# iit_hawkrod_main_board.net
KiCad netlist of a schematic drawn in EAGLE
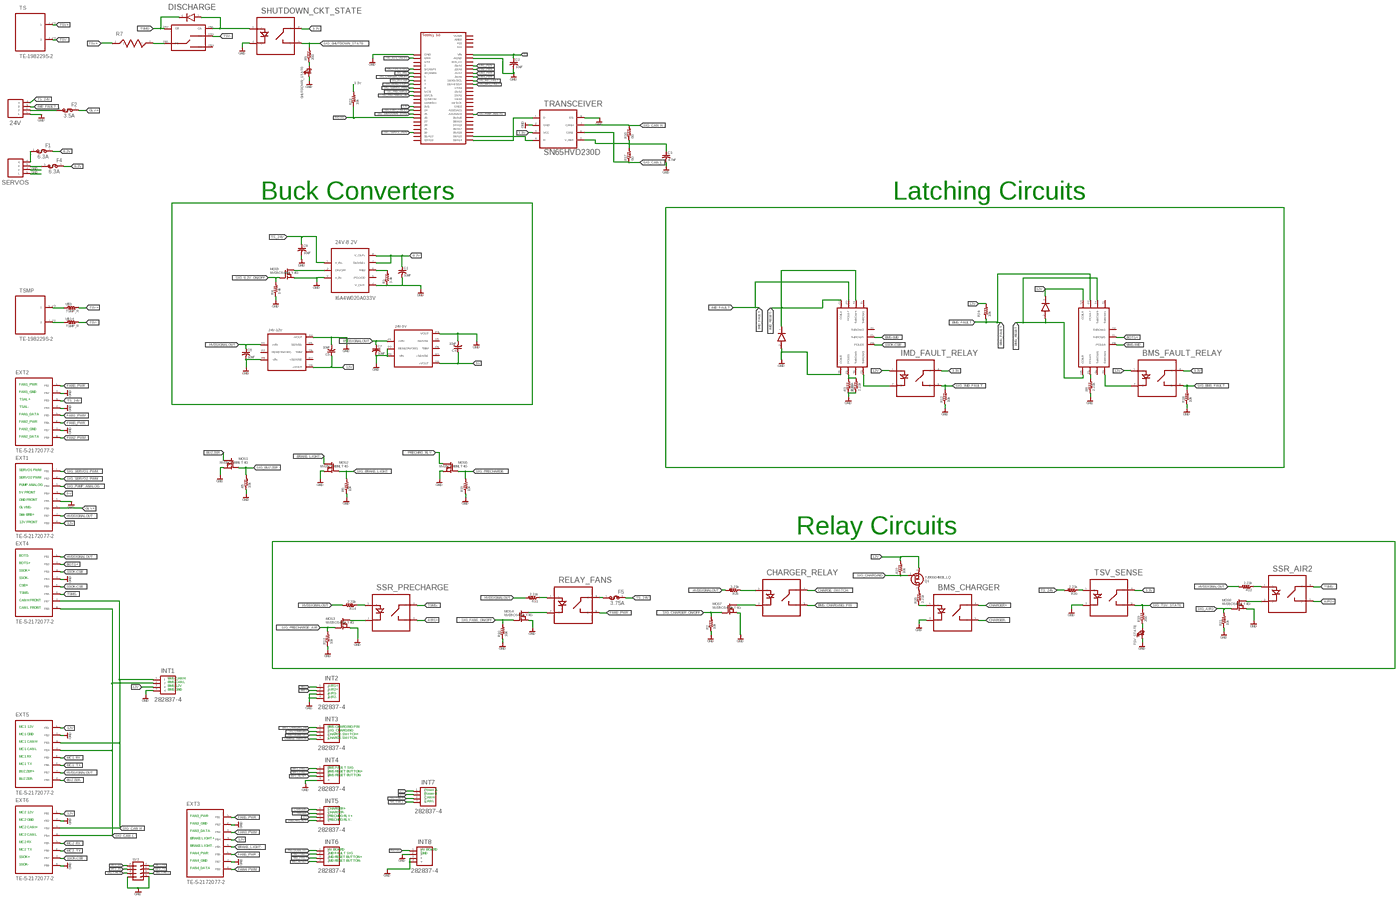
[diagram p0: schematic, sheet 1, overview]
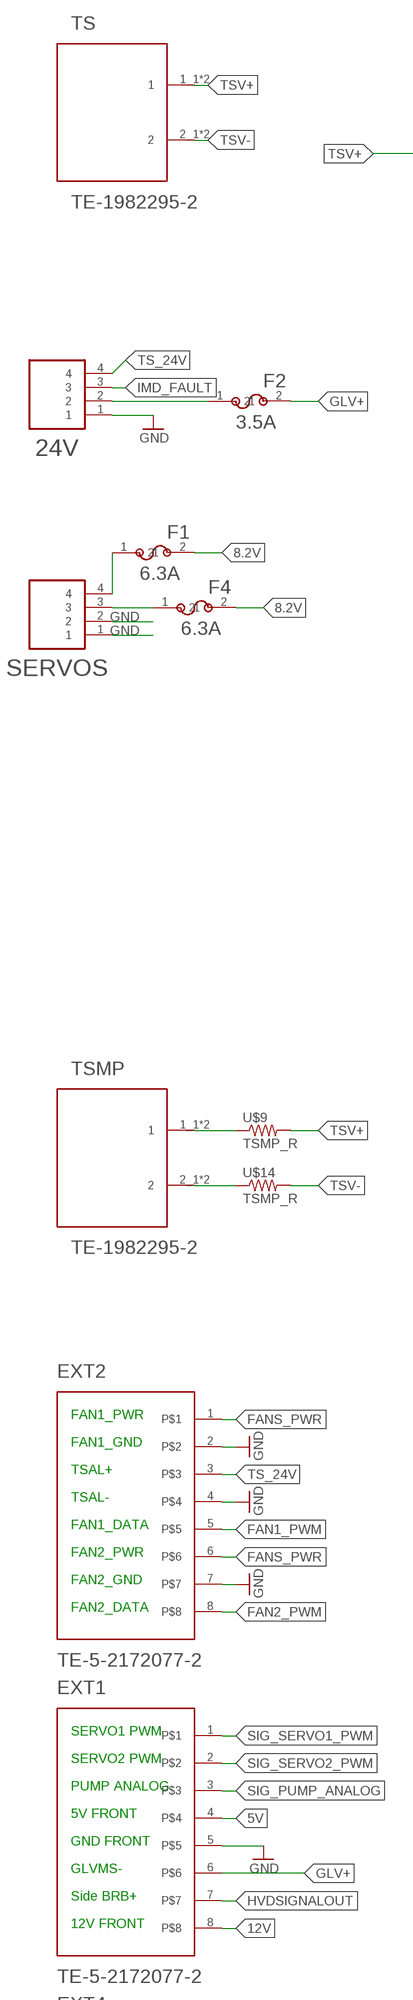
[diagram p1: schematic, sheet 1, part 1 of 5]
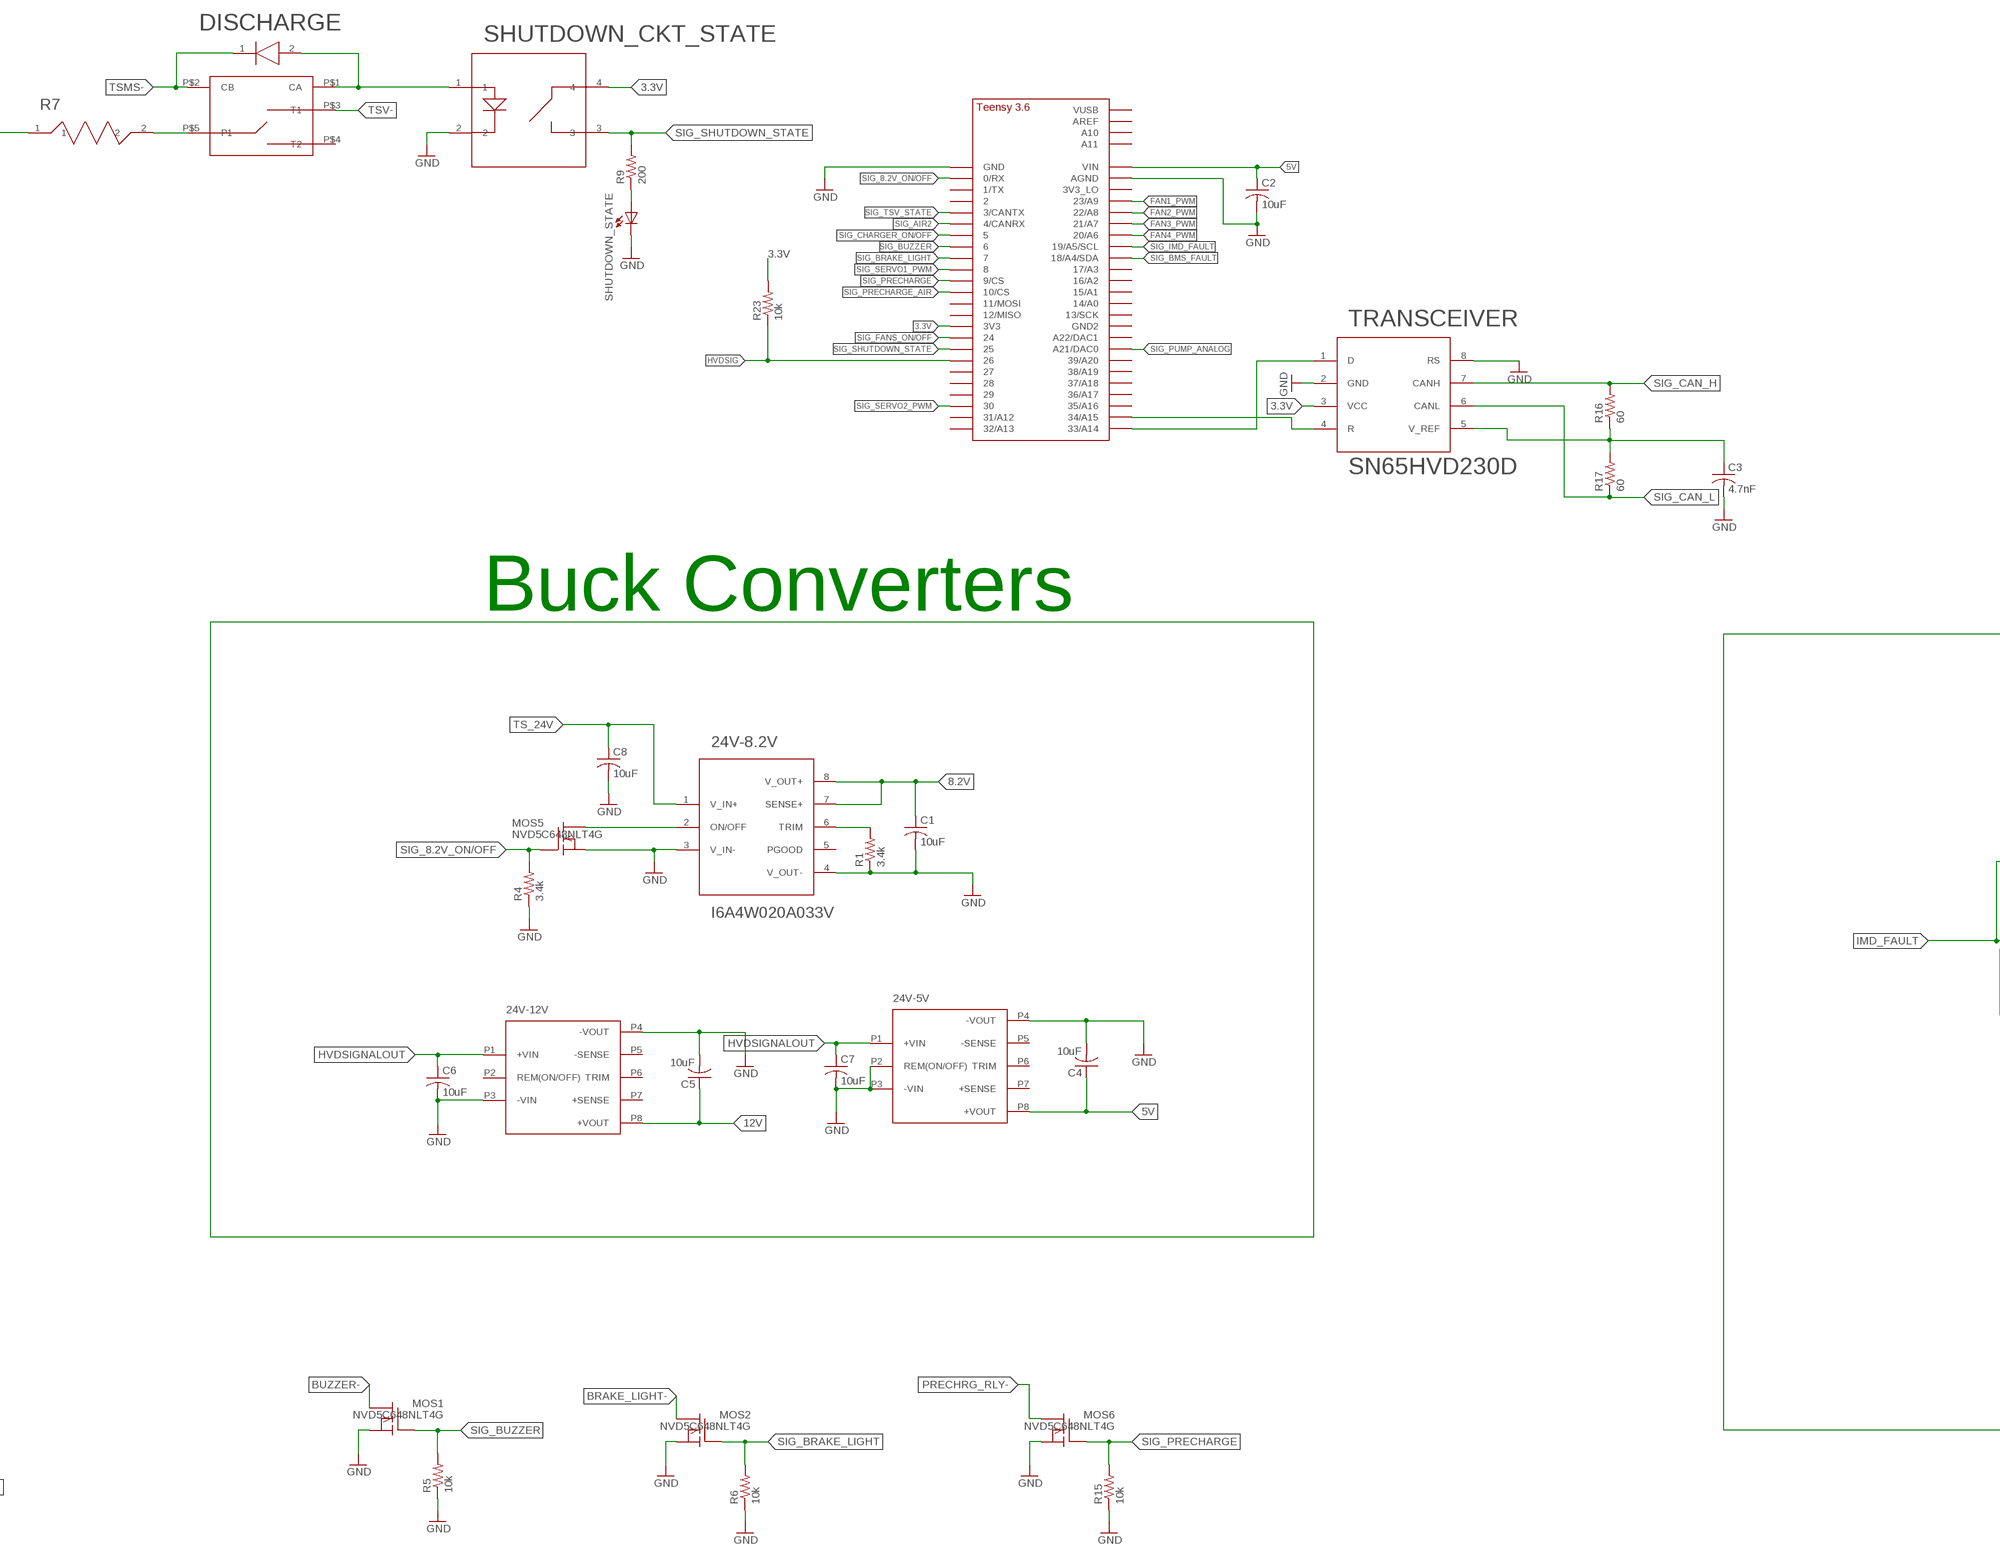
[diagram p2: schematic, sheet 1, part 2 of 5]
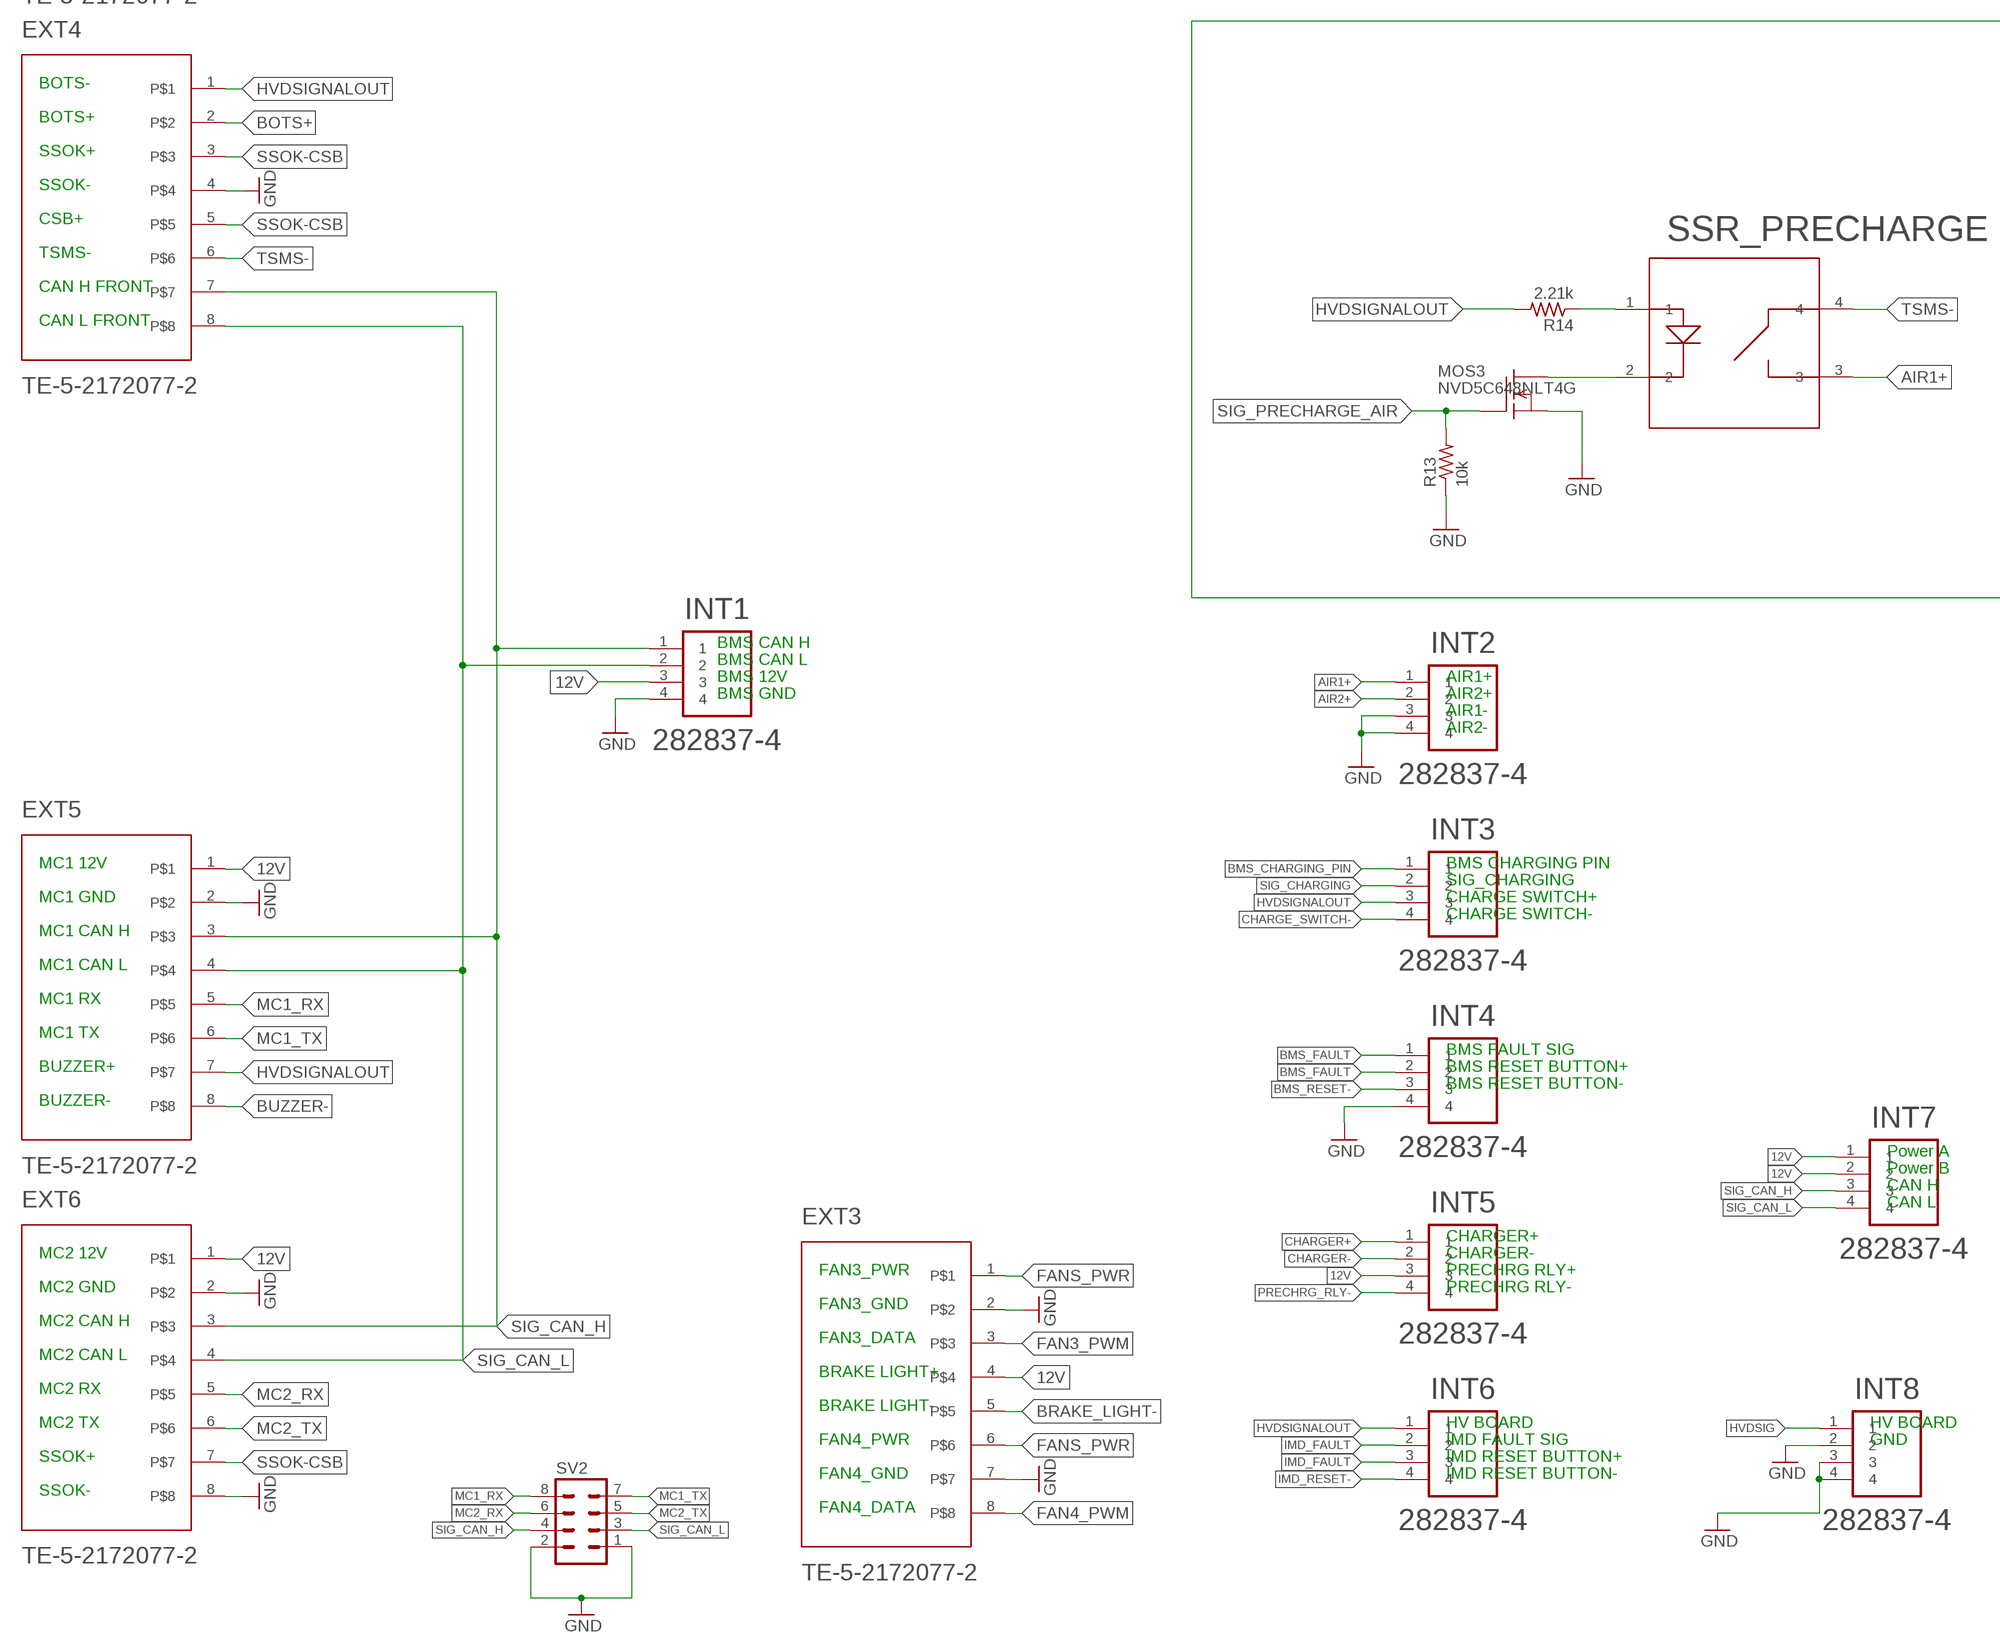
[diagram p3: schematic, sheet 1, part 3 of 5]
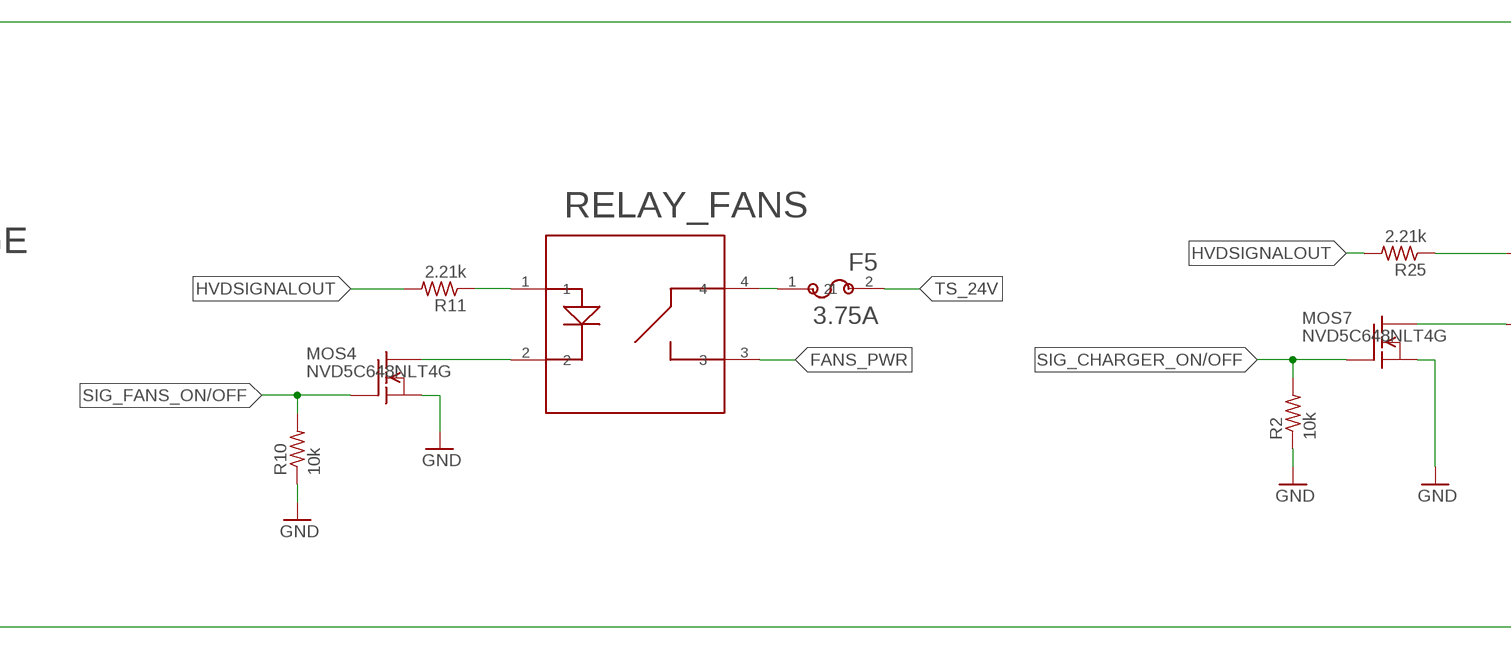
[diagram p4: schematic, sheet 1, part 4 of 5]
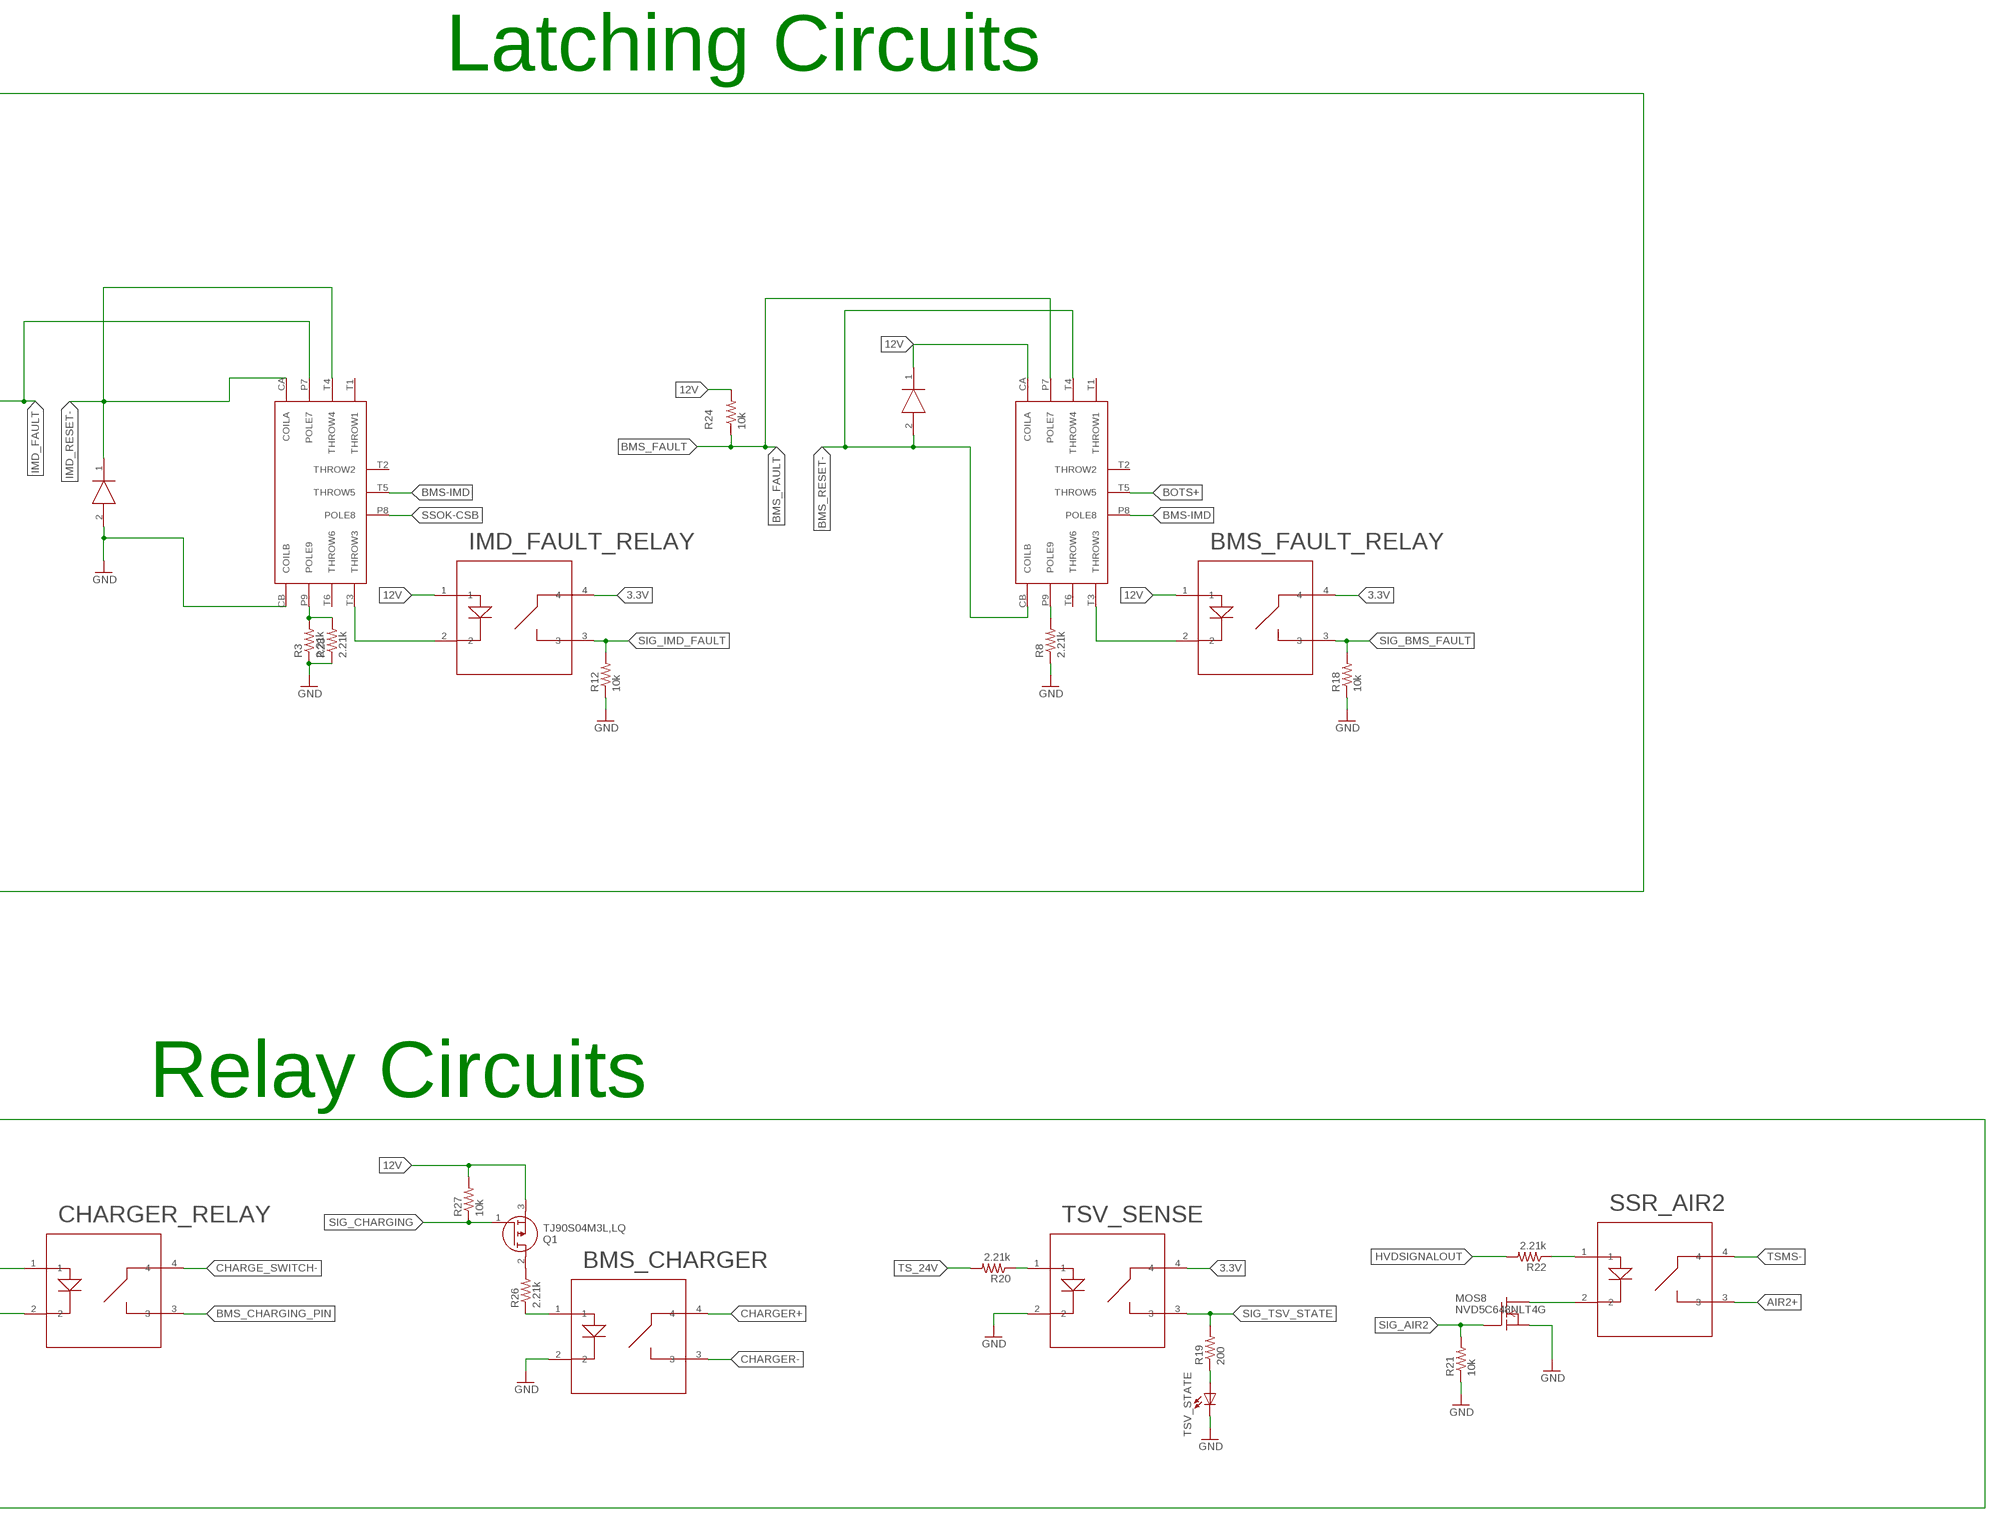
[diagram p5: schematic, sheet 1, part 5 of 5]

(export (version "E")
  (design (tool "Eeschema 10.0.6"))
  (components
    (comp (ref "24V")
      (value "282837-4")
      (footprint "eagle-import:TE_282837-4")
      (fields (field (name "MANUFACTURER") "TE CONNECTIVITY"))
      (libsource (lib "eagle-import") (part "282837-4"))
    )
    (comp (ref "24V-5V")
      (value "IRS-5/10-Q12NF-C")
      (footprint "eagle-import:IRS-5_10-Q12NF-C")
      (libsource (lib "eagle-import") (part "IRS-5/10-Q12NF-C"))
    )
    (comp (ref "24V-8.2V")
      (value "I6A4W020A033V")
      (footprint "eagle-import:I6A4W020A033V")
      (libsource (lib "eagle-import") (part "I6A4W020A033V"))
    )
    (comp (ref "24V-12V")
      (value "IRS-5/10-Q12NF-C")
      (footprint "eagle-import:IRS-5_10-Q12NF-C")
      (libsource (lib "eagle-import") (part "IRS-5/10-Q12NF-C"))
    )
    (comp (ref "BMS_CHARGER")
      (value "G3VM-61GR2")
      (footprint "eagle-import:SOP4")
      (libsource (lib "eagle-import") (part "G3VM-61GR2"))
    )
    (comp (ref "BMS_FAULT_RELAY")
      (value "G3VM-61GR2")
      (footprint "eagle-import:SOP4")
      (libsource (lib "eagle-import") (part "G3VM-61GR2"))
    )
    (comp (ref "C1")
      (value "10uF")
      (footprint "eagle-import:C1206")
      (libsource (lib "eagle-import") (part "C-USC1206"))
    )
    (comp (ref "C2")
      (value "10uF")
      (footprint "eagle-import:C1206")
      (libsource (lib "eagle-import") (part "C-USC1206"))
    )
    (comp (ref "C3")
      (value "4.7nF")
      (footprint "eagle-import:C1206")
      (libsource (lib "eagle-import") (part "C-USC1206"))
    )
    (comp (ref "C4")
      (value "10uF")
      (footprint "eagle-import:C1206")
      (libsource (lib "eagle-import") (part "C-USC1206"))
    )
    (comp (ref "C5")
      (value "10uF")
      (footprint "eagle-import:C1206")
      (libsource (lib "eagle-import") (part "C-USC1206"))
    )
    (comp (ref "C6")
      (value "10uF")
      (footprint "eagle-import:C1206")
      (libsource (lib "eagle-import") (part "C-USC1206"))
    )
    (comp (ref "C7")
      (value "10uF")
      (footprint "eagle-import:C1206")
      (libsource (lib "eagle-import") (part "C-USC1206"))
    )
    (comp (ref "C8")
      (value "10uF")
      (footprint "eagle-import:C1206")
      (libsource (lib "eagle-import") (part "C-USC1206"))
    )
    (comp (ref "CHARGER_RELAY")
      (value "G3VM-61GR2")
      (footprint "eagle-import:SOP4")
      (libsource (lib "eagle-import") (part "G3VM-61GR2"))
    )
    (comp (ref "EXT1")
      (value "TE-5-2172077-2")
      (footprint "eagle-import:TE-5-2172077-2")
      (libsource (lib "eagle-import") (part "TE-5-2172077-2"))
    )
    (comp (ref "EXT2")
      (value "TE-5-2172077-2")
      (footprint "eagle-import:TE-5-2172077-2")
      (libsource (lib "eagle-import") (part "TE-5-2172077-2"))
    )
    (comp (ref "EXT3")
      (value "TE-5-2172077-2")
      (footprint "eagle-import:TE-5-2172077-2")
      (libsource (lib "eagle-import") (part "TE-5-2172077-2"))
    )
    (comp (ref "EXT4")
      (value "TE-5-2172077-2")
      (footprint "eagle-import:TE-5-2172077-2")
      (libsource (lib "eagle-import") (part "TE-5-2172077-2"))
    )
    (comp (ref "EXT5")
      (value "TE-5-2172077-2")
      (footprint "eagle-import:TE-5-2172077-2")
      (libsource (lib "eagle-import") (part "TE-5-2172077-2"))
    )
    (comp (ref "EXT6")
      (value "TE-5-2172077-2")
      (footprint "eagle-import:TE-5-2172077-2")
      (libsource (lib "eagle-import") (part "TE-5-2172077-2"))
    )
    (comp (ref "F1")
      (value "6.3A")
      (footprint "eagle-import:SMD_FUSE_HOLDER")
      (libsource (lib "eagle-import") (part "SMD_FUSE_HOLDER"))
    )
    (comp (ref "F2")
      (value "3.5A")
      (footprint "eagle-import:SMD_FUSE_HOLDER")
      (libsource (lib "eagle-import") (part "SMD_FUSE_HOLDER"))
    )
    (comp (ref "F4")
      (value "6.3A")
      (footprint "eagle-import:SMD_FUSE_HOLDER")
      (libsource (lib "eagle-import") (part "SMD_FUSE_HOLDER"))
    )
    (comp (ref "F5")
      (value "3.75A")
      (footprint "eagle-import:SMD_FUSE_HOLDER")
      (libsource (lib "eagle-import") (part "SMD_FUSE_HOLDER"))
    )
    (comp (ref "IMD_FAULT_RELAY")
      (value "G3VM-61GR2")
      (footprint "eagle-import:SOP4")
      (libsource (lib "eagle-import") (part "G3VM-61GR2"))
    )
    (comp (ref "INT1")
      (value "282837-4")
      (footprint "eagle-import:TE_282837-4")
      (fields (field (name "MANUFACTURER") "TE CONNECTIVITY"))
      (libsource (lib "eagle-import") (part "282837-4"))
    )
    (comp (ref "INT2")
      (value "282837-4")
      (footprint "eagle-import:TE_282837-4")
      (fields (field (name "MANUFACTURER") "TE CONNECTIVITY"))
      (libsource (lib "eagle-import") (part "282837-4"))
    )
    (comp (ref "INT3")
      (value "282837-4")
      (footprint "eagle-import:TE_282837-4")
      (fields (field (name "MANUFACTURER") "TE CONNECTIVITY"))
      (libsource (lib "eagle-import") (part "282837-4"))
    )
    (comp (ref "INT4")
      (value "282837-4")
      (footprint "eagle-import:TE_282837-4")
      (fields (field (name "MANUFACTURER") "TE CONNECTIVITY"))
      (libsource (lib "eagle-import") (part "282837-4"))
    )
    (comp (ref "INT5")
      (value "282837-4")
      (footprint "eagle-import:TE_282837-4")
      (fields (field (name "MANUFACTURER") "TE CONNECTIVITY"))
      (libsource (lib "eagle-import") (part "282837-4"))
    )
    (comp (ref "INT6")
      (value "282837-4")
      (footprint "eagle-import:TE_282837-4")
      (fields (field (name "MANUFACTURER") "TE CONNECTIVITY"))
      (libsource (lib "eagle-import") (part "282837-4"))
    )
    (comp (ref "INT7")
      (value "282837-4")
      (footprint "eagle-import:TE_282837-4")
      (fields (field (name "MANUFACTURER") "TE CONNECTIVITY"))
      (libsource (lib "eagle-import") (part "282837-4"))
    )
    (comp (ref "INT8")
      (value "282837-4")
      (footprint "eagle-import:TE_282837-4")
      (fields (field (name "MANUFACTURER") "TE CONNECTIVITY"))
      (libsource (lib "eagle-import") (part "282837-4"))
    )
    (comp (ref "MOS1")
      (value "NVD5C648NLT4G")
      (footprint "eagle-import:DPAK")
      (libsource (lib "eagle-import") (part "NVD5C648NLT4G"))
    )
    (comp (ref "MOS2")
      (value "NVD5C648NLT4G")
      (footprint "eagle-import:DPAK")
      (libsource (lib "eagle-import") (part "NVD5C648NLT4G"))
    )
    (comp (ref "MOS3")
      (value "NVD5C648NLT4G")
      (footprint "eagle-import:DPAK")
      (libsource (lib "eagle-import") (part "NVD5C648NLT4G"))
    )
    (comp (ref "MOS4")
      (value "NVD5C648NLT4G")
      (footprint "eagle-import:DPAK")
      (libsource (lib "eagle-import") (part "NVD5C648NLT4G"))
    )
    (comp (ref "MOS5")
      (value "NVD5C648NLT4G")
      (footprint "eagle-import:DPAK")
      (libsource (lib "eagle-import") (part "NVD5C648NLT4G"))
    )
    (comp (ref "MOS6")
      (value "NVD5C648NLT4G")
      (footprint "eagle-import:DPAK")
      (libsource (lib "eagle-import") (part "NVD5C648NLT4G"))
    )
    (comp (ref "MOS7")
      (value "NVD5C648NLT4G")
      (footprint "eagle-import:DPAK")
      (libsource (lib "eagle-import") (part "NVD5C648NLT4G"))
    )
    (comp (ref "MOS8")
      (value "NVD5C648NLT4G")
      (footprint "eagle-import:DPAK")
      (libsource (lib "eagle-import") (part "NVD5C648NLT4G"))
    )
    (comp (ref "Q1")
      (value "TJ90S04M3L,LQ")
      (footprint "eagle-import:TJ90S04M3LLQ")
      (fields (field (name "MOUSER_PART_NUMBER") "757-TJ90S04M3LLQ"))
      (libsource (lib "eagle-import") (part "TJ90S04M3L,LQ"))
    )
    (comp (ref "R1")
      (value "3.4k")
      (footprint "eagle-import:R1206")
      (libsource (lib "eagle-import") (part "R-US_R1206"))
    )
    (comp (ref "R2")
      (value "10k")
      (footprint "eagle-import:R1206")
      (libsource (lib "eagle-import") (part "R-US_R1206"))
    )
    (comp (ref "R3")
      (value "2.21k")
      (footprint "eagle-import:R1206")
      (libsource (lib "eagle-import") (part "R-US_R1206"))
    )
    (comp (ref "R4")
      (value "3.4k")
      (footprint "eagle-import:R1206")
      (libsource (lib "eagle-import") (part "R-US_R1206"))
    )
    (comp (ref "R5")
      (value "10k")
      (footprint "eagle-import:M1206")
      (libsource (lib "eagle-import") (part "R-US_M1206"))
    )
    (comp (ref "R6")
      (value "10k")
      (footprint "eagle-import:M1206")
      (libsource (lib "eagle-import") (part "R-US_M1206"))
    )
    (comp (ref "R7")
      (value "HSA501K0J")
      (footprint "eagle-import:HSA501K0J")
      (libsource (lib "eagle-import") (part "HSA501K0J"))
    )
    (comp (ref "R8")
      (value "2.21k")
      (footprint "eagle-import:R1206")
      (libsource (lib "eagle-import") (part "R-US_R1206"))
    )
    (comp (ref "R9")
      (value "200")
      (footprint "eagle-import:M1206")
      (libsource (lib "eagle-import") (part "R-US_M1206"))
    )
    (comp (ref "R10")
      (value "10k")
      (footprint "eagle-import:R1206")
      (libsource (lib "eagle-import") (part "R-US_R1206"))
    )
    (comp (ref "R11")
      (value "2.21k")
      (footprint "eagle-import:R1206")
      (libsource (lib "eagle-import") (part "R-US_R1206"))
    )
    (comp (ref "R12")
      (value "10k")
      (footprint "eagle-import:M1206")
      (libsource (lib "eagle-import") (part "R-US_M1206"))
    )
    (comp (ref "R13")
      (value "10k")
      (footprint "eagle-import:M1206")
      (libsource (lib "eagle-import") (part "R-US_M1206"))
    )
    (comp (ref "R14")
      (value "2.21k")
      (footprint "eagle-import:R1206")
      (libsource (lib "eagle-import") (part "R-US_R1206"))
    )
    (comp (ref "R15")
      (value "10k")
      (footprint "eagle-import:M1206")
      (libsource (lib "eagle-import") (part "R-US_M1206"))
    )
    (comp (ref "R16")
      (value "60")
      (footprint "eagle-import:R1206")
      (libsource (lib "eagle-import") (part "R-US_R1206"))
    )
    (comp (ref "R17")
      (value "60")
      (footprint "eagle-import:R1206")
      (libsource (lib "eagle-import") (part "R-US_R1206"))
    )
    (comp (ref "R18")
      (value "10k")
      (footprint "eagle-import:M1206")
      (libsource (lib "eagle-import") (part "R-US_M1206"))
    )
    (comp (ref "R19")
      (value "200")
      (footprint "eagle-import:M1206")
      (libsource (lib "eagle-import") (part "R-US_M1206"))
    )
    (comp (ref "R20")
      (value "2.21k")
      (footprint "eagle-import:R1206")
      (libsource (lib "eagle-import") (part "R-US_R1206"))
    )
    (comp (ref "R21")
      (value "10k")
      (footprint "eagle-import:M1206")
      (libsource (lib "eagle-import") (part "R-US_M1206"))
    )
    (comp (ref "R22")
      (value "2.21k")
      (footprint "eagle-import:R1206")
      (libsource (lib "eagle-import") (part "R-US_R1206"))
    )
    (comp (ref "R23")
      (value "10k")
      (footprint "eagle-import:M1206")
      (libsource (lib "eagle-import") (part "R-US_M1206"))
    )
    (comp (ref "R24")
      (value "10k")
      (footprint "eagle-import:M1206")
      (libsource (lib "eagle-import") (part "R-US_M1206"))
    )
    (comp (ref "R25")
      (value "2.21k")
      (footprint "eagle-import:R1206")
      (libsource (lib "eagle-import") (part "R-US_R1206"))
    )
    (comp (ref "R26")
      (value "2.21k")
      (footprint "eagle-import:R1206")
      (libsource (lib "eagle-import") (part "R-US_R1206"))
    )
    (comp (ref "R27")
      (value "10k")
      (footprint "eagle-import:R1206")
      (libsource (lib "eagle-import") (part "R-US_R1206"))
    )
    (comp (ref "R28")
      (value "2.21k")
      (footprint "eagle-import:R1206")
      (libsource (lib "eagle-import") (part "R-US_R1206"))
    )
    (comp (ref "RELAY_FANS")
      (value "G3VM-61GR2")
      (footprint "eagle-import:SOP4")
      (libsource (lib "eagle-import") (part "G3VM-61GR2"))
    )
    (comp (ref "SERVOS")
      (value "282837-4")
      (footprint "eagle-import:TE_282837-4")
      (fields (field (name "MANUFACTURER") "TE CONNECTIVITY"))
      (libsource (lib "eagle-import") (part "282837-4"))
    )
    (comp (ref "SHUTDOWN_CKT_STATE")
      (value "G3VM-61GR2")
      (footprint "eagle-import:SOP4")
      (libsource (lib "eagle-import") (part "G3VM-61GR2"))
    )
    (comp (ref "SHUTDOWN_STATE")
      (value "LEDCHIP-LED0805")
      (footprint "eagle-import:CHIP-LED0805")
      (libsource (lib "eagle-import") (part "LEDCHIP-LED0805"))
    )
    (comp (ref "SSR_AIR2")
      (value "G3VM-61GR2")
      (footprint "eagle-import:SOP4")
      (libsource (lib "eagle-import") (part "G3VM-61GR2"))
    )
    (comp (ref "SSR_PRECHARGE")
      (value "G3VM-61GR2")
      (footprint "eagle-import:SOP4")
      (libsource (lib "eagle-import") (part "G3VM-61GR2"))
    )
    (comp (ref "SV2")
      (value "MA04-2")
      (footprint "eagle-import:MA04-2")
      (libsource (lib "eagle-import") (part "MA04-2"))
    )
    (comp (ref "TEENSY_3.6")
      (value "TEENSY_3.5/3.6_BASIC")
      (footprint "eagle-import:TEENSY_3.5_3.6_BASIC")
      (libsource (lib "eagle-import") (part "TEENSY_3.5/3.6_BASIC"))
    )
    (comp (ref "TRANSCEIVER")
      (value "SN65HVD230D")
      (footprint "eagle-import:R-PDSO-8")
      (libsource (lib "eagle-import") (part "SN65HVD230D"))
    )
    (comp (ref "TS")
      (value "TE-1982295-2")
      (footprint "eagle-import:TE-1982295-2")
      (libsource (lib "eagle-import") (part "TE-1982295-2"))
    )
    (comp (ref "TSMP")
      (value "TE-1982295-2")
      (footprint "eagle-import:TE-1982295-2")
      (libsource (lib "eagle-import") (part "TE-1982295-2"))
    )
    (comp (ref "TSV_SENSE")
      (value "G3VM-61GR2")
      (footprint "eagle-import:SOP4")
      (libsource (lib "eagle-import") (part "SAE_2020(2019Updated)_G3VM-61GR2"))
    )
    (comp (ref "TSV_STATE")
      (value "LEDCHIP-LED0805")
      (footprint "eagle-import:CHIP-LED0805")
      (libsource (lib "eagle-import") (part "LEDCHIP-LED0805"))
    )
    (comp (ref "U$1")
      (value "G2RL-1-HA")
      (footprint "eagle-import:G2RL-1-HA")
      (libsource (lib "eagle-import") (part "G2RL-1-HA"))
    )
    (comp (ref "U$3")
      (value "CS1M-E3/H")
      (footprint "eagle-import:DO-214AC")
      (libsource (lib "eagle-import") (part "CS1M-E3/H"))
    )
    (comp (ref "U$4")
      (value "CS1M-E3/H")
      (footprint "eagle-import:DO-214AC")
      (libsource (lib "eagle-import") (part "CS1M-E3/H"))
    )
    (comp (ref "U$5")
      (value "CS1M-E3/H")
      (footprint "eagle-import:DO-214AC")
      (libsource (lib "eagle-import") (part "CS1M-E3/H"))
    )
    (comp (ref "U$6")
      (value "27E046_RELAY_MOUNT")
      (footprint "eagle-import:27E046_RELAY_MOUNT")
      (libsource (lib "eagle-import") (part "27E046_RELAY_MOUNT"))
    )
    (comp (ref "U$7")
      (value "27E046_RELAY_MOUNT")
      (footprint "eagle-import:27E046_RELAY_MOUNT")
      (libsource (lib "eagle-import") (part "27E046_RELAY_MOUNT"))
    )
    (comp (ref "U$9")
      (value "TSMP_R")
      (footprint "eagle-import:TSMP_R")
      (libsource (lib "eagle-import") (part "TSMP_R"))
    )
    (comp (ref "U$14")
      (value "TSMP_R")
      (footprint "eagle-import:TSMP_R")
      (libsource (lib "eagle-import") (part "TSMP_R"))
    )
  )
  (nets
    (net (code "1") (name "3.3V") (class "Default")
      (node (ref "BMS_FAULT_RELAY") (pin "4") (pinfunction "4_4") (pintype "bidirectional"))
      (node (ref "IMD_FAULT_RELAY") (pin "4") (pinfunction "4_4") (pintype "bidirectional"))
      (node (ref "R23") (pin "2") (pinfunction "2_2") (pintype "passive"))
      (node (ref "SHUTDOWN_CKT_STATE") (pin "4") (pinfunction "4_4") (pintype "bidirectional"))
      (node (ref "TEENSY_3.6") (pin "3V3") (pinfunction "3V3_3V3") (pintype "bidirectional"))
      (node (ref "TRANSCEIVER") (pin "3") (pinfunction "VCC_3") (pintype "power_in"))
      (node (ref "TSV_SENSE") (pin "4") (pinfunction "4_4") (pintype "bidirectional"))
    )
    (net (code "2") (name "5V") (class "Default")
      (node (ref "24V-5V") (pin "P8") (pinfunction "+VOUT_P8") (pintype "bidirectional"))
      (node (ref "C2") (pin "1") (pinfunction "1_1") (pintype "passive"))
      (node (ref "C4") (pin "1") (pinfunction "1_1") (pintype "passive"))
      (node (ref "EXT1") (pin "4") (pinfunction "P$4_4") (pintype "bidirectional"))
      (node (ref "TEENSY_3.6") (pin "VIN") (pinfunction "VIN_VIN") (pintype "bidirectional"))
    )
    (net (code "3") (name "8.2V") (class "Default")
      (node (ref "24V-8.2V") (pin "7") (pinfunction "SENSE+_7") (pintype "bidirectional"))
      (node (ref "24V-8.2V") (pin "8") (pinfunction "V_OUT+_8") (pintype "bidirectional"))
      (node (ref "C1") (pin "1") (pinfunction "1_1") (pintype "passive"))
      (node (ref "F1") (pin "2") (pinfunction "2_2") (pintype "bidirectional"))
      (node (ref "F4") (pin "2") (pinfunction "2_2") (pintype "bidirectional"))
    )
    (net (code "4") (name "12V") (class "Default")
      (node (ref "24V-12V") (pin "P8") (pinfunction "+VOUT_P8") (pintype "bidirectional"))
      (node (ref "BMS_FAULT_RELAY") (pin "1") (pinfunction "1_1") (pintype "bidirectional"))
      (node (ref "C5") (pin "1") (pinfunction "1_1") (pintype "passive"))
      (node (ref "EXT1") (pin "8") (pinfunction "P$8_8") (pintype "bidirectional"))
      (node (ref "EXT3") (pin "4") (pinfunction "P$4_4") (pintype "bidirectional"))
      (node (ref "EXT5") (pin "1") (pinfunction "P$1_1") (pintype "bidirectional"))
      (node (ref "EXT6") (pin "1") (pinfunction "P$1_1") (pintype "bidirectional"))
      (node (ref "IMD_FAULT_RELAY") (pin "1") (pinfunction "1_1") (pintype "bidirectional"))
      (node (ref "INT1") (pin "3") (pinfunction "3_3") (pintype "passive"))
      (node (ref "INT5") (pin "3") (pinfunction "3_3") (pintype "passive"))
      (node (ref "INT7") (pin "1") (pinfunction "1_1") (pintype "passive"))
      (node (ref "INT7") (pin "2") (pinfunction "2_2") (pintype "passive"))
      (node (ref "Q1") (pin "3") (pinfunction "S_3") (pintype "bidirectional"))
      (node (ref "R24") (pin "2") (pinfunction "2_2") (pintype "passive"))
      (node (ref "R27") (pin "2") (pinfunction "2_2") (pintype "passive"))
      (node (ref "U$5") (pin "1") (pinfunction "2_1") (pintype "bidirectional"))
      (node (ref "U$7") (pin "CA") (pinfunction "COILA_CA") (pintype "bidirectional"))
    )
    (net (code "5") (name "AIR1+") (class "Default")
      (node (ref "INT2") (pin "1") (pinfunction "1_1") (pintype "passive"))
      (node (ref "SSR_PRECHARGE") (pin "3") (pinfunction "3_3") (pintype "bidirectional"))
    )
    (net (code "6") (name "AIR2+") (class "Default")
      (node (ref "INT2") (pin "2") (pinfunction "2_2") (pintype "passive"))
      (node (ref "SSR_AIR2") (pin "3") (pinfunction "3_3") (pintype "bidirectional"))
    )
    (net (code "7") (name "BMS-IMD") (class "Default")
      (node (ref "U$6") (pin "T5") (pinfunction "THROW5_T5") (pintype "bidirectional"))
      (node (ref "U$7") (pin "P8") (pinfunction "POLE8_P8") (pintype "bidirectional"))
    )
    (net (code "8") (name "BMS_CHARGING_PIN") (class "Default")
      (node (ref "CHARGER_RELAY") (pin "3") (pinfunction "3_3") (pintype "bidirectional"))
      (node (ref "INT3") (pin "1") (pinfunction "1_1") (pintype "passive"))
    )
    (net (code "9") (name "BMS_FAULT") (class "Default")
      (node (ref "INT4") (pin "1") (pinfunction "1_1") (pintype "passive"))
      (node (ref "INT4") (pin "2") (pinfunction "2_2") (pintype "passive"))
      (node (ref "R24") (pin "1") (pinfunction "1_1") (pintype "passive"))
      (node (ref "U$7") (pin "P7") (pinfunction "POLE7_P7") (pintype "bidirectional"))
    )
    (net (code "10") (name "BMS_RESET-") (class "Default")
      (node (ref "INT4") (pin "3") (pinfunction "3_3") (pintype "passive"))
      (node (ref "U$5") (pin "2") (pinfunction "1_2") (pintype "bidirectional"))
      (node (ref "U$7") (pin "CB") (pinfunction "COILB_CB") (pintype "bidirectional"))
      (node (ref "U$7") (pin "T4") (pinfunction "THROW4_T4") (pintype "bidirectional"))
    )
    (net (code "11") (name "BOTS+") (class "Default")
      (node (ref "EXT4") (pin "2") (pinfunction "P$2_2") (pintype "bidirectional"))
      (node (ref "U$7") (pin "T5") (pinfunction "THROW5_T5") (pintype "bidirectional"))
    )
    (net (code "12") (name "BRAKE_LIGHT-") (class "Default")
      (node (ref "EXT3") (pin "5") (pinfunction "P$5_5") (pintype "bidirectional"))
      (node (ref "MOS2") (pin "4") (pinfunction "D_4") (pintype "passive"))
    )
    (net (code "13") (name "BUZZER-") (class "Default")
      (node (ref "EXT5") (pin "8") (pinfunction "P$8_8") (pintype "bidirectional"))
      (node (ref "MOS1") (pin "4") (pinfunction "D_4") (pintype "passive"))
    )
    (net (code "14") (name "CHARGER+") (class "Default")
      (node (ref "BMS_CHARGER") (pin "4") (pinfunction "4_4") (pintype "bidirectional"))
      (node (ref "INT5") (pin "1") (pinfunction "1_1") (pintype "passive"))
    )
    (net (code "15") (name "CHARGER-") (class "Default")
      (node (ref "BMS_CHARGER") (pin "3") (pinfunction "3_3") (pintype "bidirectional"))
      (node (ref "INT5") (pin "2") (pinfunction "2_2") (pintype "passive"))
    )
    (net (code "16") (name "CHARGE_SWITCH-") (class "Default")
      (node (ref "CHARGER_RELAY") (pin "4") (pinfunction "4_4") (pintype "bidirectional"))
      (node (ref "INT3") (pin "4") (pinfunction "4_4") (pintype "passive"))
    )
    (net (code "17") (name "FAN1_PWM") (class "Default")
      (node (ref "EXT2") (pin "5") (pinfunction "P$5_5") (pintype "bidirectional"))
      (node (ref "TEENSY_3.6") (pin "23/A9") (pinfunction "23/A9_23/A9") (pintype "bidirectional"))
    )
    (net (code "18") (name "FAN2_PWM") (class "Default")
      (node (ref "EXT2") (pin "8") (pinfunction "P$8_8") (pintype "bidirectional"))
      (node (ref "TEENSY_3.6") (pin "22/A8") (pinfunction "22/A8_22/A8") (pintype "bidirectional"))
    )
    (net (code "19") (name "FAN3_PWM") (class "Default")
      (node (ref "EXT3") (pin "3") (pinfunction "P$3_3") (pintype "bidirectional"))
      (node (ref "TEENSY_3.6") (pin "21/A7") (pinfunction "21/A7_21/A7") (pintype "bidirectional"))
    )
    (net (code "20") (name "FAN4_PWM") (class "Default")
      (node (ref "EXT3") (pin "8") (pinfunction "P$8_8") (pintype "bidirectional"))
      (node (ref "TEENSY_3.6") (pin "20/A6") (pinfunction "20/A6_20/A6") (pintype "bidirectional"))
    )
    (net (code "21") (name "FANS_PWR") (class "Default")
      (node (ref "EXT2") (pin "1") (pinfunction "P$1_1") (pintype "bidirectional"))
      (node (ref "EXT2") (pin "6") (pinfunction "P$6_6") (pintype "bidirectional"))
      (node (ref "EXT3") (pin "1") (pinfunction "P$1_1") (pintype "bidirectional"))
      (node (ref "EXT3") (pin "6") (pinfunction "P$6_6") (pintype "bidirectional"))
      (node (ref "RELAY_FANS") (pin "3") (pinfunction "3_3") (pintype "bidirectional"))
    )
    (net (code "22") (name "GLV+") (class "Default")
      (node (ref "EXT1") (pin "6") (pinfunction "P$6_6") (pintype "bidirectional"))
      (node (ref "F2") (pin "2") (pinfunction "2_2") (pintype "bidirectional"))
    )
    (net (code "23") (name "GND") (class "Default")
      (node (ref "24V") (pin "1") (pinfunction "1_1") (pintype "passive"))
      (node (ref "24V-12V") (pin "P3") (pinfunction "-VIN_P3") (pintype "bidirectional"))
      (node (ref "24V-12V") (pin "P4") (pinfunction "-VOUT_P4") (pintype "bidirectional"))
      (node (ref "24V-5V") (pin "P2") (pinfunction "REM(ON/OFF)_P2") (pintype "bidirectional"))
      (node (ref "24V-5V") (pin "P3") (pinfunction "-VIN_P3") (pintype "bidirectional"))
      (node (ref "24V-5V") (pin "P4") (pinfunction "-VOUT_P4") (pintype "bidirectional"))
      (node (ref "24V-8.2V") (pin "3") (pinfunction "V_IN-_3") (pintype "bidirectional"))
      (node (ref "24V-8.2V") (pin "4") (pinfunction "V_OUT-_4") (pintype "bidirectional"))
      (node (ref "BMS_CHARGER") (pin "2") (pinfunction "2_2") (pintype "bidirectional"))
      (node (ref "C1") (pin "2") (pinfunction "2_2") (pintype "passive"))
      (node (ref "C2") (pin "2") (pinfunction "2_2") (pintype "passive"))
      (node (ref "C3") (pin "2") (pinfunction "2_2") (pintype "passive"))
      (node (ref "C4") (pin "2") (pinfunction "2_2") (pintype "passive"))
      (node (ref "C5") (pin "2") (pinfunction "2_2") (pintype "passive"))
      (node (ref "C6") (pin "2") (pinfunction "2_2") (pintype "passive"))
      (node (ref "C7") (pin "2") (pinfunction "2_2") (pintype "passive"))
      (node (ref "C8") (pin "2") (pinfunction "2_2") (pintype "passive"))
      (node (ref "EXT1") (pin "5") (pinfunction "P$5_5") (pintype "bidirectional"))
      (node (ref "EXT2") (pin "2") (pinfunction "P$2_2") (pintype "bidirectional"))
      (node (ref "EXT2") (pin "4") (pinfunction "P$4_4") (pintype "bidirectional"))
      (node (ref "EXT2") (pin "7") (pinfunction "P$7_7") (pintype "bidirectional"))
      (node (ref "EXT3") (pin "2") (pinfunction "P$2_2") (pintype "bidirectional"))
      (node (ref "EXT3") (pin "7") (pinfunction "P$7_7") (pintype "bidirectional"))
      (node (ref "EXT4") (pin "4") (pinfunction "P$4_4") (pintype "bidirectional"))
      (node (ref "EXT5") (pin "2") (pinfunction "P$2_2") (pintype "bidirectional"))
      (node (ref "EXT6") (pin "2") (pinfunction "P$2_2") (pintype "bidirectional"))
      (node (ref "EXT6") (pin "8") (pinfunction "P$8_8") (pintype "bidirectional"))
      (node (ref "INT1") (pin "4") (pinfunction "4_4") (pintype "passive"))
      (node (ref "INT2") (pin "3") (pinfunction "3_3") (pintype "passive"))
      (node (ref "INT2") (pin "4") (pinfunction "4_4") (pintype "passive"))
      (node (ref "INT4") (pin "4") (pinfunction "4_4") (pintype "passive"))
      (node (ref "INT8") (pin "2") (pinfunction "2_2") (pintype "passive"))
      (node (ref "INT8") (pin "3") (pinfunction "3_3") (pintype "passive"))
      (node (ref "INT8") (pin "4") (pinfunction "4_4") (pintype "passive"))
      (node (ref "MOS1") (pin "3") (pinfunction "S_3") (pintype "passive"))
      (node (ref "MOS2") (pin "3") (pinfunction "S_3") (pintype "passive"))
      (node (ref "MOS3") (pin "3") (pinfunction "S_3") (pintype "passive"))
      (node (ref "MOS4") (pin "3") (pinfunction "S_3") (pintype "passive"))
      (node (ref "MOS5") (pin "3") (pinfunction "S_3") (pintype "passive"))
      (node (ref "MOS6") (pin "3") (pinfunction "S_3") (pintype "passive"))
      (node (ref "MOS7") (pin "3") (pinfunction "S_3") (pintype "passive"))
      (node (ref "MOS8") (pin "3") (pinfunction "S_3") (pintype "passive"))
      (node (ref "R1") (pin "1") (pinfunction "1_1") (pintype "passive"))
      (node (ref "R10") (pin "1") (pinfunction "1_1") (pintype "passive"))
      (node (ref "R12") (pin "1") (pinfunction "1_1") (pintype "passive"))
      (node (ref "R13") (pin "1") (pinfunction "1_1") (pintype "passive"))
      (node (ref "R15") (pin "1") (pinfunction "1_1") (pintype "passive"))
      (node (ref "R18") (pin "1") (pinfunction "1_1") (pintype "passive"))
      (node (ref "R2") (pin "1") (pinfunction "1_1") (pintype "passive"))
      (node (ref "R21") (pin "1") (pinfunction "1_1") (pintype "passive"))
      (node (ref "R28") (pin "1") (pinfunction "1_1") (pintype "passive"))
      (node (ref "R3") (pin "1") (pinfunction "1_1") (pintype "passive"))
      (node (ref "R4") (pin "1") (pinfunction "1_1") (pintype "passive"))
      (node (ref "R5") (pin "1") (pinfunction "1_1") (pintype "passive"))
      (node (ref "R6") (pin "1") (pinfunction "1_1") (pintype "passive"))
      (node (ref "R8") (pin "1") (pinfunction "1_1") (pintype "passive"))
      (node (ref "SERVOS") (pin "1") (pinfunction "1_1") (pintype "passive"))
      (node (ref "SERVOS") (pin "2") (pinfunction "2_2") (pintype "passive"))
      (node (ref "SHUTDOWN_CKT_STATE") (pin "2") (pinfunction "2_2") (pintype "bidirectional"))
      (node (ref "SHUTDOWN_STATE") (pin "C") (pinfunction "C_C") (pintype "passive"))
      (node (ref "SV2") (pin "1") (pinfunction "1_1") (pintype "passive"))
      (node (ref "SV2") (pin "2") (pinfunction "2_2") (pintype "passive"))
      (node (ref "TEENSY_3.6") (pin "AGND") (pinfunction "AGND_AGND") (pintype "bidirectional"))
      (node (ref "TEENSY_3.6") (pin "GND") (pinfunction "GND_GND") (pintype "bidirectional"))
      (node (ref "TRANSCEIVER") (pin "2") (pinfunction "GND_2") (pintype "power_in"))
      (node (ref "TRANSCEIVER") (pin "8") (pinfunction "RS_8") (pintype "bidirectional"))
      (node (ref "TSV_SENSE") (pin "2") (pinfunction "2_2") (pintype "bidirectional"))
      (node (ref "TSV_STATE") (pin "C") (pinfunction "C_C") (pintype "passive"))
      (node (ref "U$4") (pin "2") (pinfunction "1_2") (pintype "bidirectional"))
      (node (ref "U$6") (pin "CB") (pinfunction "COILB_CB") (pintype "bidirectional"))
    )
    (net (code "24") (name "HVDSIG") (class "Default")
      (node (ref "INT8") (pin "1") (pinfunction "1_1") (pintype "passive"))
      (node (ref "R23") (pin "1") (pinfunction "1_1") (pintype "passive"))
      (node (ref "TEENSY_3.6") (pin "26") (pinfunction "26_26") (pintype "bidirectional"))
    )
    (net (code "25") (name "HVDSIGNALOUT") (class "Default")
      (node (ref "24V-12V") (pin "P1") (pinfunction "+VIN_P1") (pintype "bidirectional"))
      (node (ref "24V-5V") (pin "P1") (pinfunction "+VIN_P1") (pintype "bidirectional"))
      (node (ref "C6") (pin "1") (pinfunction "1_1") (pintype "passive"))
      (node (ref "C7") (pin "1") (pinfunction "1_1") (pintype "passive"))
      (node (ref "EXT1") (pin "7") (pinfunction "P$7_7") (pintype "bidirectional"))
      (node (ref "EXT4") (pin "1") (pinfunction "P$1_1") (pintype "bidirectional"))
      (node (ref "EXT5") (pin "7") (pinfunction "P$7_7") (pintype "bidirectional"))
      (node (ref "INT3") (pin "3") (pinfunction "3_3") (pintype "passive"))
      (node (ref "INT6") (pin "1") (pinfunction "1_1") (pintype "passive"))
      (node (ref "R11") (pin "2") (pinfunction "2_2") (pintype "passive"))
      (node (ref "R14") (pin "2") (pinfunction "2_2") (pintype "passive"))
      (node (ref "R22") (pin "2") (pinfunction "2_2") (pintype "passive"))
      (node (ref "R25") (pin "2") (pinfunction "2_2") (pintype "passive"))
    )
    (net (code "26") (name "IMD_FAULT") (class "Default")
      (node (ref "24V") (pin "3") (pinfunction "3_3") (pintype "passive"))
      (node (ref "INT6") (pin "2") (pinfunction "2_2") (pintype "passive"))
      (node (ref "INT6") (pin "3") (pinfunction "3_3") (pintype "passive"))
      (node (ref "U$6") (pin "P7") (pinfunction "POLE7_P7") (pintype "bidirectional"))
    )
    (net (code "27") (name "IMD_RESET-") (class "Default")
      (node (ref "INT6") (pin "4") (pinfunction "4_4") (pintype "passive"))
      (node (ref "U$4") (pin "1") (pinfunction "2_1") (pintype "bidirectional"))
      (node (ref "U$6") (pin "CA") (pinfunction "COILA_CA") (pintype "bidirectional"))
      (node (ref "U$6") (pin "T4") (pinfunction "THROW4_T4") (pintype "bidirectional"))
    )
    (net (code "28") (name "MC1_RX") (class "Default")
      (node (ref "EXT5") (pin "5") (pinfunction "P$5_5") (pintype "bidirectional"))
      (node (ref "SV2") (pin "8") (pinfunction "8_8") (pintype "passive"))
    )
    (net (code "29") (name "MC1_TX") (class "Default")
      (node (ref "EXT5") (pin "6") (pinfunction "P$6_6") (pintype "bidirectional"))
      (node (ref "SV2") (pin "7") (pinfunction "7_7") (pintype "passive"))
    )
    (net (code "30") (name "MC2_RX") (class "Default")
      (node (ref "EXT6") (pin "5") (pinfunction "P$5_5") (pintype "bidirectional"))
      (node (ref "SV2") (pin "6") (pinfunction "6_6") (pintype "passive"))
    )
    (net (code "31") (name "MC2_TX") (class "Default")
      (node (ref "EXT6") (pin "6") (pinfunction "P$6_6") (pintype "bidirectional"))
      (node (ref "SV2") (pin "5") (pinfunction "5_5") (pintype "passive"))
    )
    (net (code "32") (name "Net-(24V-8.2V-ON{slash}OFF)") (class "Default")
      (node (ref "24V-8.2V") (pin "2") (pinfunction "ON/OFF_2") (pintype "bidirectional"))
      (node (ref "MOS5") (pin "4") (pinfunction "D_4") (pintype "passive"))
    )
    (net (code "33") (name "Net-(24V-8.2V-TRIM)") (class "Default")
      (node (ref "24V-8.2V") (pin "6") (pinfunction "TRIM_6") (pintype "bidirectional"))
      (node (ref "R1") (pin "2") (pinfunction "2_2") (pintype "passive"))
    )
    (net (code "34") (name "Net-(24V-Pad2)") (class "Default")
      (node (ref "24V") (pin "2") (pinfunction "2_2") (pintype "passive"))
      (node (ref "F2") (pin "1") (pinfunction "1_1") (pintype "bidirectional"))
    )
    (net (code "35") (name "Net-(BMS_CHARGER-Pad1)") (class "Default")
      (node (ref "BMS_CHARGER") (pin "1") (pinfunction "1_1") (pintype "bidirectional"))
      (node (ref "R26") (pin "1") (pinfunction "1_1") (pintype "passive"))
    )
    (net (code "36") (name "Net-(CHARGER_RELAY-Pad1)") (class "Default")
      (node (ref "CHARGER_RELAY") (pin "1") (pinfunction "1_1") (pintype "bidirectional"))
      (node (ref "R25") (pin "1") (pinfunction "1_1") (pintype "passive"))
    )
    (net (code "37") (name "Net-(F1-Pad1)") (class "Default")
      (node (ref "F1") (pin "1") (pinfunction "1_1") (pintype "bidirectional"))
      (node (ref "SERVOS") (pin "4") (pinfunction "4_4") (pintype "passive"))
    )
    (net (code "38") (name "Net-(F4-Pad1)") (class "Default")
      (node (ref "F4") (pin "1") (pinfunction "1_1") (pintype "bidirectional"))
      (node (ref "SERVOS") (pin "3") (pinfunction "3_3") (pintype "passive"))
    )
    (net (code "39") (name "Net-(F5-Pad1)") (class "Default")
      (node (ref "F5") (pin "1") (pinfunction "1_1") (pintype "bidirectional"))
      (node (ref "RELAY_FANS") (pin "4") (pinfunction "4_4") (pintype "bidirectional"))
    )
    (net (code "40") (name "Net-(MOS3-D)") (class "Default")
      (node (ref "MOS3") (pin "4") (pinfunction "D_4") (pintype "passive"))
      (node (ref "SSR_PRECHARGE") (pin "2") (pinfunction "2_2") (pintype "bidirectional"))
    )
    (net (code "41") (name "Net-(MOS4-D)") (class "Default")
      (node (ref "MOS4") (pin "4") (pinfunction "D_4") (pintype "passive"))
      (node (ref "RELAY_FANS") (pin "2") (pinfunction "2_2") (pintype "bidirectional"))
    )
    (net (code "42") (name "Net-(MOS7-D)") (class "Default")
      (node (ref "CHARGER_RELAY") (pin "2") (pinfunction "2_2") (pintype "bidirectional"))
      (node (ref "MOS7") (pin "4") (pinfunction "D_4") (pintype "passive"))
    )
    (net (code "43") (name "Net-(MOS8-D)") (class "Default")
      (node (ref "MOS8") (pin "4") (pinfunction "D_4") (pintype "passive"))
      (node (ref "SSR_AIR2") (pin "2") (pinfunction "2_2") (pintype "bidirectional"))
    )
    (net (code "44") (name "Net-(Q1-D)") (class "Default")
      (node (ref "Q1") (pin "2") (pinfunction "D_2") (pintype "bidirectional"))
      (node (ref "R26") (pin "2") (pinfunction "2_2") (pintype "passive"))
    )
    (net (code "45") (name "Net-(R9-Pad1)") (class "Default")
      (node (ref "R9") (pin "1") (pinfunction "1_1") (pintype "passive"))
      (node (ref "SHUTDOWN_STATE") (pin "A") (pinfunction "A_A") (pintype "passive"))
    )
    (net (code "46") (name "Net-(R11-Pad1)") (class "Default")
      (node (ref "R11") (pin "1") (pinfunction "1_1") (pintype "passive"))
      (node (ref "RELAY_FANS") (pin "1") (pinfunction "1_1") (pintype "bidirectional"))
    )
    (net (code "47") (name "Net-(R14-Pad1)") (class "Default")
      (node (ref "R14") (pin "1") (pinfunction "1_1") (pintype "passive"))
      (node (ref "SSR_PRECHARGE") (pin "1") (pinfunction "1_1") (pintype "bidirectional"))
    )
    (net (code "48") (name "Net-(R19-Pad1)") (class "Default")
      (node (ref "R19") (pin "1") (pinfunction "1_1") (pintype "passive"))
      (node (ref "TSV_STATE") (pin "A") (pinfunction "A_A") (pintype "passive"))
    )
    (net (code "49") (name "Net-(R20-Pad1)") (class "Default")
      (node (ref "R20") (pin "1") (pinfunction "1_1") (pintype "passive"))
      (node (ref "TSV_SENSE") (pin "1") (pinfunction "1_1") (pintype "bidirectional"))
    )
    (net (code "50") (name "Net-(R22-Pad1)") (class "Default")
      (node (ref "R22") (pin "1") (pinfunction "1_1") (pintype "passive"))
      (node (ref "SSR_AIR2") (pin "1") (pinfunction "1_1") (pintype "bidirectional"))
    )
    (net (code "51") (name "Net-(TRANSCEIVER-D)") (class "Default")
      (node (ref "TEENSY_3.6") (pin "33/A14") (pinfunction "33/A14_33/A14") (pintype "bidirectional"))
      (node (ref "TRANSCEIVER") (pin "1") (pinfunction "D_1") (pintype "bidirectional"))
    )
    (net (code "52") (name "Net-(TRANSCEIVER-R)") (class "Default")
      (node (ref "TEENSY_3.6") (pin "34/A15") (pinfunction "34/A15_34/A15") (pintype "bidirectional"))
      (node (ref "TRANSCEIVER") (pin "4") (pinfunction "R_4") (pintype "bidirectional"))
    )
    (net (code "53") (name "Net-(TRANSCEIVER-V_REF)") (class "Default")
      (node (ref "C3") (pin "1") (pinfunction "1_1") (pintype "passive"))
      (node (ref "R16") (pin "1") (pinfunction "1_1") (pintype "passive"))
      (node (ref "R17") (pin "2") (pinfunction "2_2") (pintype "passive"))
      (node (ref "TRANSCEIVER") (pin "5") (pinfunction "V_REF_5") (pintype "bidirectional"))
    )
    (net (code "54") (name "Net-(U$1-CA)") (class "Default")
      (node (ref "SHUTDOWN_CKT_STATE") (pin "1") (pinfunction "1_1") (pintype "bidirectional"))
      (node (ref "U$1") (pin "P$1") (pinfunction "CA_P$1") (pintype "bidirectional"))
      (node (ref "U$3") (pin "2") (pinfunction "1_2") (pintype "bidirectional"))
    )
    (net (code "55") (name "Net-(U$1-P1)") (class "Default")
      (node (ref "R7") (pin "2") (pinfunction "2_2") (pintype "bidirectional"))
      (node (ref "U$1") (pin "P$5") (pinfunction "P1_P$5") (pintype "bidirectional"))
    )
    (net (code "56") (name "Net-(U$6-POLE9)") (class "Default")
      (node (ref "R28") (pin "2") (pinfunction "2_2") (pintype "passive"))
      (node (ref "R3") (pin "2") (pinfunction "2_2") (pintype "passive"))
      (node (ref "U$6") (pin "P9") (pinfunction "POLE9_P9") (pintype "bidirectional"))
    )
    (net (code "57") (name "Net-(U$6-THROW3)") (class "Default")
      (node (ref "IMD_FAULT_RELAY") (pin "2") (pinfunction "2_2") (pintype "bidirectional"))
      (node (ref "U$6") (pin "T3") (pinfunction "THROW3_T3") (pintype "bidirectional"))
    )
    (net (code "58") (name "Net-(U$7-POLE9)") (class "Default")
      (node (ref "R8") (pin "2") (pinfunction "2_2") (pintype "passive"))
      (node (ref "U$7") (pin "P9") (pinfunction "POLE9_P9") (pintype "bidirectional"))
    )
    (net (code "59") (name "Net-(U$7-THROW3)") (class "Default")
      (node (ref "BMS_FAULT_RELAY") (pin "2") (pinfunction "2_2") (pintype "bidirectional"))
      (node (ref "U$7") (pin "T3") (pinfunction "THROW3_T3") (pintype "bidirectional"))
    )
    (net (code "60") (name "Net-(U$9-1)") (class "Default")
      (node (ref "TSMP") (pin "1_1") (pinfunction "1_1_1") (pintype "power_in"))
      (node (ref "TSMP") (pin "1_2") (pinfunction "1_1_2") (pintype "power_in"))
      (node (ref "U$9") (pin "T1") (pinfunction "1_T1") (pintype "passive"))
    )
    (net (code "61") (name "Net-(U$14-1)") (class "Default")
      (node (ref "TSMP") (pin "2_1") (pinfunction "2_2_1") (pintype "power_in"))
      (node (ref "TSMP") (pin "2_2") (pinfunction "2_2_2") (pintype "power_in"))
      (node (ref "U$14") (pin "T1") (pinfunction "1_T1") (pintype "passive"))
    )
    (net (code "62") (name "PRECHRG_RLY-") (class "Default")
      (node (ref "INT5") (pin "4") (pinfunction "4_4") (pintype "passive"))
      (node (ref "MOS6") (pin "4") (pinfunction "D_4") (pintype "passive"))
    )
    (net (code "63") (name "SIG_8.2V_ON{slash}OFF") (class "Default")
      (node (ref "MOS5") (pin "1") (pinfunction "G_1") (pintype "passive"))
      (node (ref "R4") (pin "2") (pinfunction "2_2") (pintype "passive"))
      (node (ref "TEENSY_3.6") (pin "0/RX") (pinfunction "0/RX_0/RX") (pintype "bidirectional"))
    )
    (net (code "64") (name "SIG_AIR2") (class "Default")
      (node (ref "MOS8") (pin "1") (pinfunction "G_1") (pintype "passive"))
      (node (ref "R21") (pin "2") (pinfunction "2_2") (pintype "passive"))
      (node (ref "TEENSY_3.6") (pin "4/CANRX") (pinfunction "4/CANRX_4/CANRX") (pintype "bidirectional"))
    )
    (net (code "65") (name "SIG_BMS_FAULT") (class "Default")
      (node (ref "BMS_FAULT_RELAY") (pin "3") (pinfunction "3_3") (pintype "bidirectional"))
      (node (ref "R18") (pin "2") (pinfunction "2_2") (pintype "passive"))
      (node (ref "TEENSY_3.6") (pin "18/A4/SDA") (pinfunction "18/A4/SDA_18/A4/SDA") (pintype "bidirectional"))
    )
    (net (code "66") (name "SIG_BRAKE_LIGHT") (class "Default")
      (node (ref "MOS2") (pin "1") (pinfunction "G_1") (pintype "passive"))
      (node (ref "R6") (pin "2") (pinfunction "2_2") (pintype "passive"))
      (node (ref "TEENSY_3.6") (pin "7") (pinfunction "7_7") (pintype "bidirectional"))
    )
    (net (code "67") (name "SIG_BUZZER") (class "Default")
      (node (ref "MOS1") (pin "1") (pinfunction "G_1") (pintype "passive"))
      (node (ref "R5") (pin "2") (pinfunction "2_2") (pintype "passive"))
      (node (ref "TEENSY_3.6") (pin "6") (pinfunction "6_6") (pintype "bidirectional"))
    )
    (net (code "68") (name "SIG_CAN_H") (class "Default")
      (node (ref "EXT4") (pin "7") (pinfunction "P$7_7") (pintype "bidirectional"))
      (node (ref "EXT5") (pin "3") (pinfunction "P$3_3") (pintype "bidirectional"))
      (node (ref "EXT6") (pin "3") (pinfunction "P$3_3") (pintype "bidirectional"))
      (node (ref "INT1") (pin "1") (pinfunction "1_1") (pintype "passive"))
      (node (ref "INT7") (pin "3") (pinfunction "3_3") (pintype "passive"))
      (node (ref "R16") (pin "2") (pinfunction "2_2") (pintype "passive"))
      (node (ref "SV2") (pin "4") (pinfunction "4_4") (pintype "passive"))
      (node (ref "TRANSCEIVER") (pin "7") (pinfunction "CANH_7") (pintype "bidirectional"))
    )
    (net (code "69") (name "SIG_CAN_L") (class "Default")
      (node (ref "EXT4") (pin "8") (pinfunction "P$8_8") (pintype "bidirectional"))
      (node (ref "EXT5") (pin "4") (pinfunction "P$4_4") (pintype "bidirectional"))
      (node (ref "EXT6") (pin "4") (pinfunction "P$4_4") (pintype "bidirectional"))
      (node (ref "INT1") (pin "2") (pinfunction "2_2") (pintype "passive"))
      (node (ref "INT7") (pin "4") (pinfunction "4_4") (pintype "passive"))
      (node (ref "R17") (pin "1") (pinfunction "1_1") (pintype "passive"))
      (node (ref "SV2") (pin "3") (pinfunction "3_3") (pintype "passive"))
      (node (ref "TRANSCEIVER") (pin "6") (pinfunction "CANL_6") (pintype "bidirectional"))
    )
    (net (code "70") (name "SIG_CHARGER_ON{slash}OFF") (class "Default")
      (node (ref "MOS7") (pin "1") (pinfunction "G_1") (pintype "passive"))
      (node (ref "R2") (pin "2") (pinfunction "2_2") (pintype "passive"))
      (node (ref "TEENSY_3.6") (pin "5") (pinfunction "5_5") (pintype "bidirectional"))
    )
    (net (code "71") (name "SIG_CHARGING") (class "Default")
      (node (ref "INT3") (pin "2") (pinfunction "2_2") (pintype "passive"))
      (node (ref "Q1") (pin "1") (pinfunction "G_1") (pintype "bidirectional"))
      (node (ref "R27") (pin "1") (pinfunction "1_1") (pintype "passive"))
    )
    (net (code "72") (name "SIG_FANS_ON{slash}OFF") (class "Default")
      (node (ref "MOS4") (pin "1") (pinfunction "G_1") (pintype "passive"))
      (node (ref "R10") (pin "2") (pinfunction "2_2") (pintype "passive"))
      (node (ref "TEENSY_3.6") (pin "24") (pinfunction "24_24") (pintype "bidirectional"))
    )
    (net (code "73") (name "SIG_IMD_FAULT") (class "Default")
      (node (ref "IMD_FAULT_RELAY") (pin "3") (pinfunction "3_3") (pintype "bidirectional"))
      (node (ref "R12") (pin "2") (pinfunction "2_2") (pintype "passive"))
      (node (ref "TEENSY_3.6") (pin "19/A5/SCL") (pinfunction "19/A5/SCL_19/A5/SCL") (pintype "bidirectional"))
    )
    (net (code "74") (name "SIG_PRECHARGE") (class "Default")
      (node (ref "MOS6") (pin "1") (pinfunction "G_1") (pintype "passive"))
      (node (ref "R15") (pin "2") (pinfunction "2_2") (pintype "passive"))
      (node (ref "TEENSY_3.6") (pin "9/CS") (pinfunction "9/CS_9/CS") (pintype "bidirectional"))
    )
    (net (code "75") (name "SIG_PRECHARGE_AIR") (class "Default")
      (node (ref "MOS3") (pin "1") (pinfunction "G_1") (pintype "passive"))
      (node (ref "R13") (pin "2") (pinfunction "2_2") (pintype "passive"))
      (node (ref "TEENSY_3.6") (pin "10/CS") (pinfunction "10/CS_10/CS") (pintype "bidirectional"))
    )
    (net (code "76") (name "SIG_PUMP_ANALOG") (class "Default")
      (node (ref "EXT1") (pin "3") (pinfunction "P$3_3") (pintype "bidirectional"))
      (node (ref "TEENSY_3.6") (pin "21/DAC0") (pinfunction "A21/DAC0_21/DAC0") (pintype "bidirectional"))
    )
    (net (code "77") (name "SIG_SERVO1_PWM") (class "Default")
      (node (ref "EXT1") (pin "1") (pinfunction "P$1_1") (pintype "bidirectional"))
      (node (ref "TEENSY_3.6") (pin "8") (pinfunction "8_8") (pintype "bidirectional"))
    )
    (net (code "78") (name "SIG_SERVO2_PWM") (class "Default")
      (node (ref "EXT1") (pin "2") (pinfunction "P$2_2") (pintype "bidirectional"))
      (node (ref "TEENSY_3.6") (pin "30") (pinfunction "30_30") (pintype "bidirectional"))
    )
    (net (code "79") (name "SIG_SHUTDOWN_STATE") (class "Default")
      (node (ref "R9") (pin "2") (pinfunction "2_2") (pintype "passive"))
      (node (ref "SHUTDOWN_CKT_STATE") (pin "3") (pinfunction "3_3") (pintype "bidirectional"))
      (node (ref "TEENSY_3.6") (pin "25") (pinfunction "25_25") (pintype "bidirectional"))
    )
    (net (code "80") (name "SIG_TSV_STATE") (class "Default")
      (node (ref "R19") (pin "2") (pinfunction "2_2") (pintype "passive"))
      (node (ref "TEENSY_3.6") (pin "3/CANTX") (pinfunction "3/CANTX_3/CANTX") (pintype "bidirectional"))
      (node (ref "TSV_SENSE") (pin "3") (pinfunction "3_3") (pintype "bidirectional"))
    )
    (net (code "81") (name "SSOK-CSB") (class "Default")
      (node (ref "EXT4") (pin "3") (pinfunction "P$3_3") (pintype "bidirectional"))
      (node (ref "EXT4") (pin "5") (pinfunction "P$5_5") (pintype "bidirectional"))
      (node (ref "EXT6") (pin "7") (pinfunction "P$7_7") (pintype "bidirectional"))
      (node (ref "U$6") (pin "P8") (pinfunction "POLE8_P8") (pintype "bidirectional"))
    )
    (net (code "82") (name "TSMS-") (class "Default")
      (node (ref "EXT4") (pin "6") (pinfunction "P$6_6") (pintype "bidirectional"))
      (node (ref "SSR_AIR2") (pin "4") (pinfunction "4_4") (pintype "bidirectional"))
      (node (ref "SSR_PRECHARGE") (pin "4") (pinfunction "4_4") (pintype "bidirectional"))
      (node (ref "U$1") (pin "P$2") (pinfunction "CB_P$2") (pintype "bidirectional"))
      (node (ref "U$3") (pin "1") (pinfunction "2_1") (pintype "bidirectional"))
    )
    (net (code "83") (name "TSV+") (class "Default")
      (node (ref "R7") (pin "1") (pinfunction "1_1") (pintype "bidirectional"))
      (node (ref "TS") (pin "1_1") (pinfunction "1_1_1") (pintype "power_in"))
      (node (ref "TS") (pin "1_2") (pinfunction "1_1_2") (pintype "power_in"))
      (node (ref "U$9") (pin "T2") (pinfunction "2_T2") (pintype "passive"))
    )
    (net (code "84") (name "TSV-") (class "Default")
      (node (ref "TS") (pin "2_1") (pinfunction "2_2_1") (pintype "power_in"))
      (node (ref "TS") (pin "2_2") (pinfunction "2_2_2") (pintype "power_in"))
      (node (ref "U$1") (pin "P$3") (pinfunction "T1_P$3") (pintype "bidirectional"))
      (node (ref "U$14") (pin "T2") (pinfunction "2_T2") (pintype "passive"))
    )
    (net (code "85") (name "TS_24V") (class "Default")
      (node (ref "24V") (pin "4") (pinfunction "4_4") (pintype "passive"))
      (node (ref "24V-8.2V") (pin "1") (pinfunction "V_IN+_1") (pintype "bidirectional"))
      (node (ref "C8") (pin "1") (pinfunction "1_1") (pintype "passive"))
      (node (ref "EXT2") (pin "3") (pinfunction "P$3_3") (pintype "bidirectional"))
      (node (ref "F5") (pin "2") (pinfunction "2_2") (pintype "bidirectional"))
      (node (ref "R20") (pin "2") (pinfunction "2_2") (pintype "passive"))
    )
    (net (code "86") (name "unconnected-(24V-5V-+SENSE-PadP7)") (class "Default")
      (node (ref "24V-5V") (pin "P7") (pinfunction "+SENSE_P7") (pintype "bidirectional"))
    )
    (net (code "87") (name "unconnected-(24V-5V--SENSE-PadP5)") (class "Default")
      (node (ref "24V-5V") (pin "P5") (pinfunction "-SENSE_P5") (pintype "bidirectional"))
    )
    (net (code "88") (name "unconnected-(24V-5V-TRIM-PadP6)") (class "Default")
      (node (ref "24V-5V") (pin "P6") (pinfunction "TRIM_P6") (pintype "bidirectional"))
    )
    (net (code "89") (name "unconnected-(24V-8.2V-PGOOD-Pad5)") (class "Default")
      (node (ref "24V-8.2V") (pin "5") (pinfunction "PGOOD_5") (pintype "bidirectional"))
    )
    (net (code "90") (name "unconnected-(24V-12V-+SENSE-PadP7)") (class "Default")
      (node (ref "24V-12V") (pin "P7") (pinfunction "+SENSE_P7") (pintype "bidirectional"))
    )
    (net (code "91") (name "unconnected-(24V-12V--SENSE-PadP5)") (class "Default")
      (node (ref "24V-12V") (pin "P5") (pinfunction "-SENSE_P5") (pintype "bidirectional"))
    )
    (net (code "92") (name "unconnected-(24V-12V-REM(ON{slash}OFF)-PadP2)") (class "Default")
      (node (ref "24V-12V") (pin "P2") (pinfunction "REM(ON/OFF)_P2") (pintype "bidirectional"))
    )
    (net (code "93") (name "unconnected-(24V-12V-TRIM-PadP6)") (class "Default")
      (node (ref "24V-12V") (pin "P6") (pinfunction "TRIM_P6") (pintype "bidirectional"))
    )
    (net (code "94") (name "unconnected-(TEENSY_3.6-Pad1{slash}TX)") (class "Default")
      (node (ref "TEENSY_3.6") (pin "1/TX") (pinfunction "1/TX_1/TX") (pintype "bidirectional"))
    )
    (net (code "95") (name "unconnected-(TEENSY_3.6-Pad2)") (class "Default")
      (node (ref "TEENSY_3.6") (pin "2") (pinfunction "2_2") (pintype "bidirectional"))
    )
    (net (code "96") (name "unconnected-(TEENSY_3.6-Pad3V3_LO)") (class "Default")
      (node (ref "TEENSY_3.6") (pin "3V3_LO") (pinfunction "3V3_LO_3V3_LO") (pintype "bidirectional"))
    )
    (net (code "97") (name "unconnected-(TEENSY_3.6-Pad11{slash}MOSI)") (class "Default")
      (node (ref "TEENSY_3.6") (pin "11/MOSI") (pinfunction "11/MOSI_11/MOSI") (pintype "bidirectional"))
    )
    (net (code "98") (name "unconnected-(TEENSY_3.6-Pad12{slash}MISO)") (class "Default")
      (node (ref "TEENSY_3.6") (pin "12/MISO") (pinfunction "12/MISO_12/MISO") (pintype "bidirectional"))
    )
    (net (code "99") (name "unconnected-(TEENSY_3.6-Pad13{slash}SCK)") (class "Default")
      (node (ref "TEENSY_3.6") (pin "13/SCK") (pinfunction "13/SCK_13/SCK") (pintype "bidirectional"))
    )
    (net (code "100") (name "unconnected-(TEENSY_3.6-Pad14{slash}A0)") (class "Default")
      (node (ref "TEENSY_3.6") (pin "14/A0") (pinfunction "14/A0_14/A0") (pintype "bidirectional"))
    )
    (net (code "101") (name "unconnected-(TEENSY_3.6-Pad15{slash}A1)") (class "Default")
      (node (ref "TEENSY_3.6") (pin "15/A1") (pinfunction "15/A1_15/A1") (pintype "bidirectional"))
    )
    (net (code "102") (name "unconnected-(TEENSY_3.6-Pad16{slash}A2)") (class "Default")
      (node (ref "TEENSY_3.6") (pin "16/A2") (pinfunction "16/A2_16/A2") (pintype "bidirectional"))
    )
    (net (code "103") (name "unconnected-(TEENSY_3.6-Pad17{slash}A3)") (class "Default")
      (node (ref "TEENSY_3.6") (pin "17/A3") (pinfunction "17/A3_17/A3") (pintype "bidirectional"))
    )
    (net (code "104") (name "unconnected-(TEENSY_3.6-Pad27)") (class "Default")
      (node (ref "TEENSY_3.6") (pin "27") (pinfunction "27_27") (pintype "bidirectional"))
    )
    (net (code "105") (name "unconnected-(TEENSY_3.6-Pad28)") (class "Default")
      (node (ref "TEENSY_3.6") (pin "28") (pinfunction "28_28") (pintype "bidirectional"))
    )
    (net (code "106") (name "unconnected-(TEENSY_3.6-Pad29)") (class "Default")
      (node (ref "TEENSY_3.6") (pin "29") (pinfunction "29_29") (pintype "bidirectional"))
    )
    (net (code "107") (name "unconnected-(TEENSY_3.6-Pad31{slash}A12)") (class "Default")
      (node (ref "TEENSY_3.6") (pin "31/A12") (pinfunction "31/A12_31/A12") (pintype "bidirectional"))
    )
    (net (code "108") (name "unconnected-(TEENSY_3.6-Pad32{slash}A13)") (class "Default")
      (node (ref "TEENSY_3.6") (pin "32/A13") (pinfunction "32/A13_32/A13") (pintype "bidirectional"))
    )
    (net (code "109") (name "unconnected-(TEENSY_3.6-Pad35{slash}A16)") (class "Default")
      (node (ref "TEENSY_3.6") (pin "35/A16") (pinfunction "35/A16_35/A16") (pintype "bidirectional"))
    )
    (net (code "110") (name "unconnected-(TEENSY_3.6-Pad36{slash}A17)") (class "Default")
      (node (ref "TEENSY_3.6") (pin "36/A17") (pinfunction "36/A17_36/A17") (pintype "bidirectional"))
    )
    (net (code "111") (name "unconnected-(TEENSY_3.6-Pad37{slash}A18)") (class "Default")
      (node (ref "TEENSY_3.6") (pin "37/A18") (pinfunction "37/A18_37/A18") (pintype "bidirectional"))
    )
    (net (code "112") (name "unconnected-(TEENSY_3.6-Pad38{slash}A19)") (class "Default")
      (node (ref "TEENSY_3.6") (pin "38/A19") (pinfunction "38/A19_38/A19") (pintype "bidirectional"))
    )
    (net (code "113") (name "unconnected-(TEENSY_3.6-Pad39{slash}A20)") (class "Default")
      (node (ref "TEENSY_3.6") (pin "39/A20") (pinfunction "39/A20_39/A20") (pintype "bidirectional"))
    )
    (net (code "114") (name "unconnected-(TEENSY_3.6-PadA10)") (class "Default")
      (node (ref "TEENSY_3.6") (pin "A10") (pinfunction "A10_A10") (pintype "bidirectional"))
    )
    (net (code "115") (name "unconnected-(TEENSY_3.6-PadA11)") (class "Default")
      (node (ref "TEENSY_3.6") (pin "A11") (pinfunction "A11_A11") (pintype "bidirectional"))
    )
    (net (code "116") (name "unconnected-(TEENSY_3.6-PadA22{slash}DAC1)") (class "Default")
      (node (ref "TEENSY_3.6") (pin "A22/DAC1") (pinfunction "A22/DAC1_A22/DAC1") (pintype "bidirectional"))
    )
    (net (code "117") (name "unconnected-(TEENSY_3.6-PadAREF)") (class "Default")
      (node (ref "TEENSY_3.6") (pin "AREF") (pinfunction "AREF_AREF") (pintype "bidirectional"))
    )
    (net (code "118") (name "unconnected-(TEENSY_3.6-PadGND2)") (class "Default")
      (node (ref "TEENSY_3.6") (pin "GND2") (pinfunction "GND2_GND2") (pintype "bidirectional"))
    )
    (net (code "119") (name "unconnected-(TEENSY_3.6-PadVUSB)") (class "Default")
      (node (ref "TEENSY_3.6") (pin "VUSB") (pinfunction "VUSB_VUSB") (pintype "bidirectional"))
    )
    (net (code "120") (name "unconnected-(U$1-T2-PadP$4)") (class "Default")
      (node (ref "U$1") (pin "P$4") (pinfunction "T2_P$4") (pintype "bidirectional"))
    )
    (net (code "121") (name "unconnected-(U$6-THROW1-PadT1)") (class "Default")
      (node (ref "U$6") (pin "T1") (pinfunction "THROW1_T1") (pintype "bidirectional"))
    )
    (net (code "122") (name "unconnected-(U$6-THROW2-PadT2)") (class "Default")
      (node (ref "U$6") (pin "T2") (pinfunction "THROW2_T2") (pintype "bidirectional"))
    )
    (net (code "123") (name "unconnected-(U$6-THROW6-PadT6)") (class "Default")
      (node (ref "U$6") (pin "T6") (pinfunction "THROW6_T6") (pintype "bidirectional"))
    )
    (net (code "124") (name "unconnected-(U$7-THROW1-PadT1)") (class "Default")
      (node (ref "U$7") (pin "T1") (pinfunction "THROW1_T1") (pintype "bidirectional"))
    )
    (net (code "125") (name "unconnected-(U$7-THROW2-PadT2)") (class "Default")
      (node (ref "U$7") (pin "T2") (pinfunction "THROW2_T2") (pintype "bidirectional"))
    )
    (net (code "126") (name "unconnected-(U$7-THROW6-PadT6)") (class "Default")
      (node (ref "U$7") (pin "T6") (pinfunction "THROW6_T6") (pintype "bidirectional"))
    )
  )
)
